# SenseLora_4G_LTE_CAT1_Gateway_V1_2.net
KiCad netlist of a schematic drawn in EAGLE
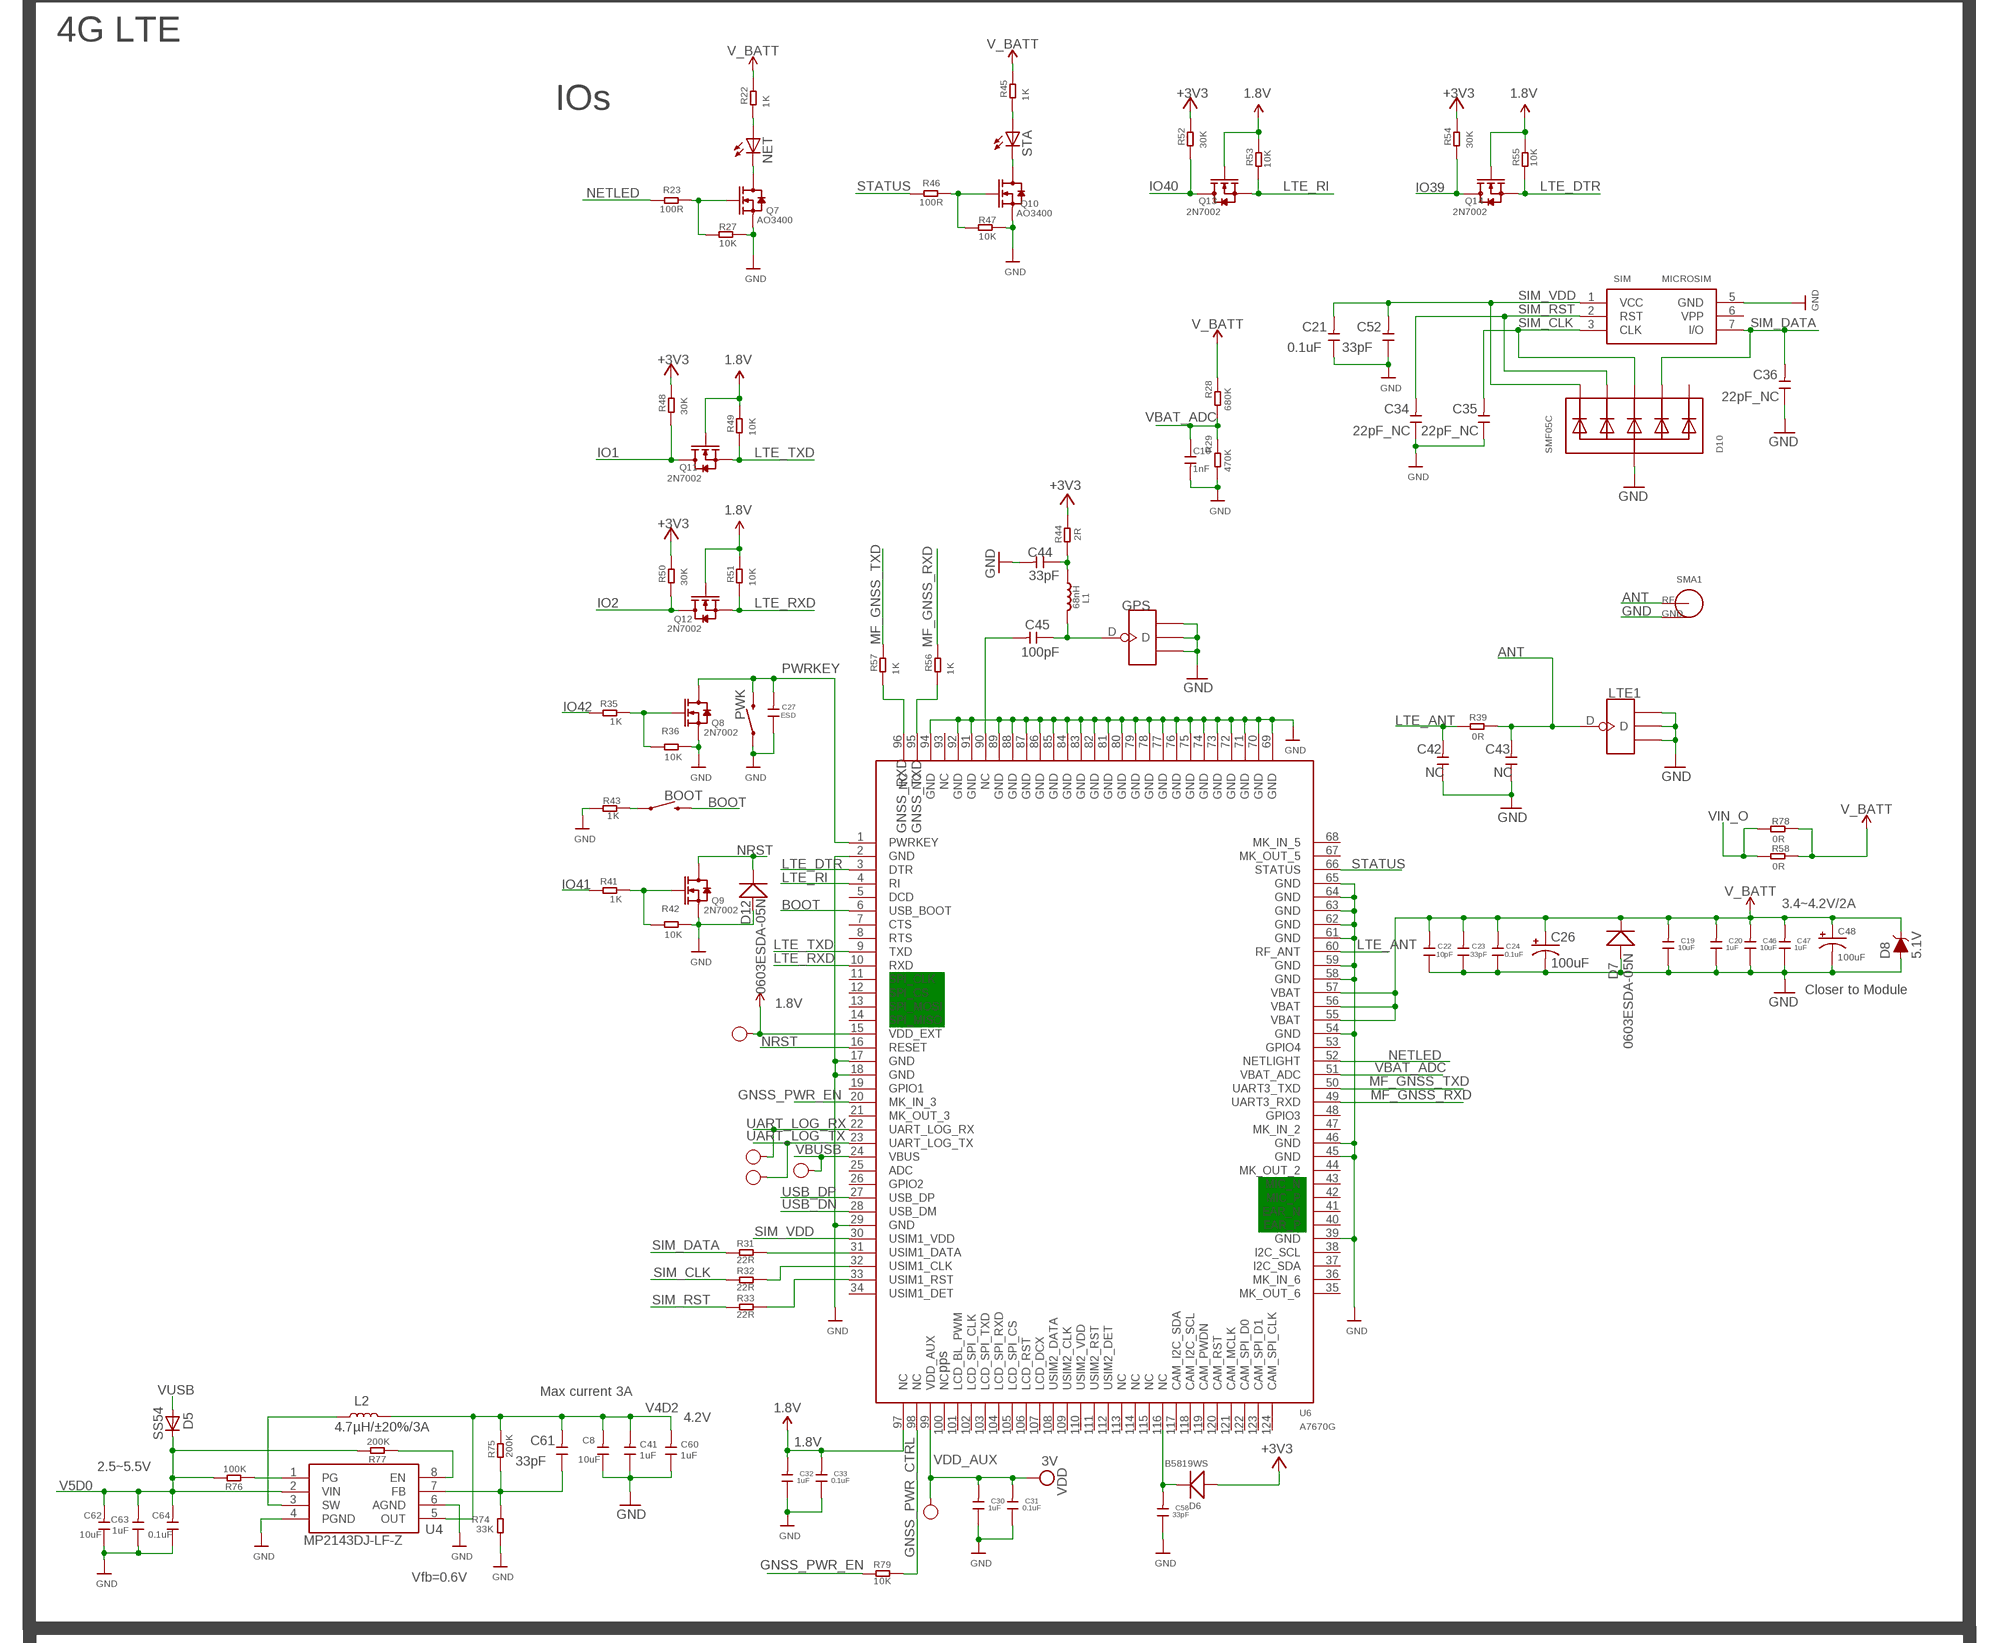
[diagram p0: schematic, sheet 1, part 1 of 2]
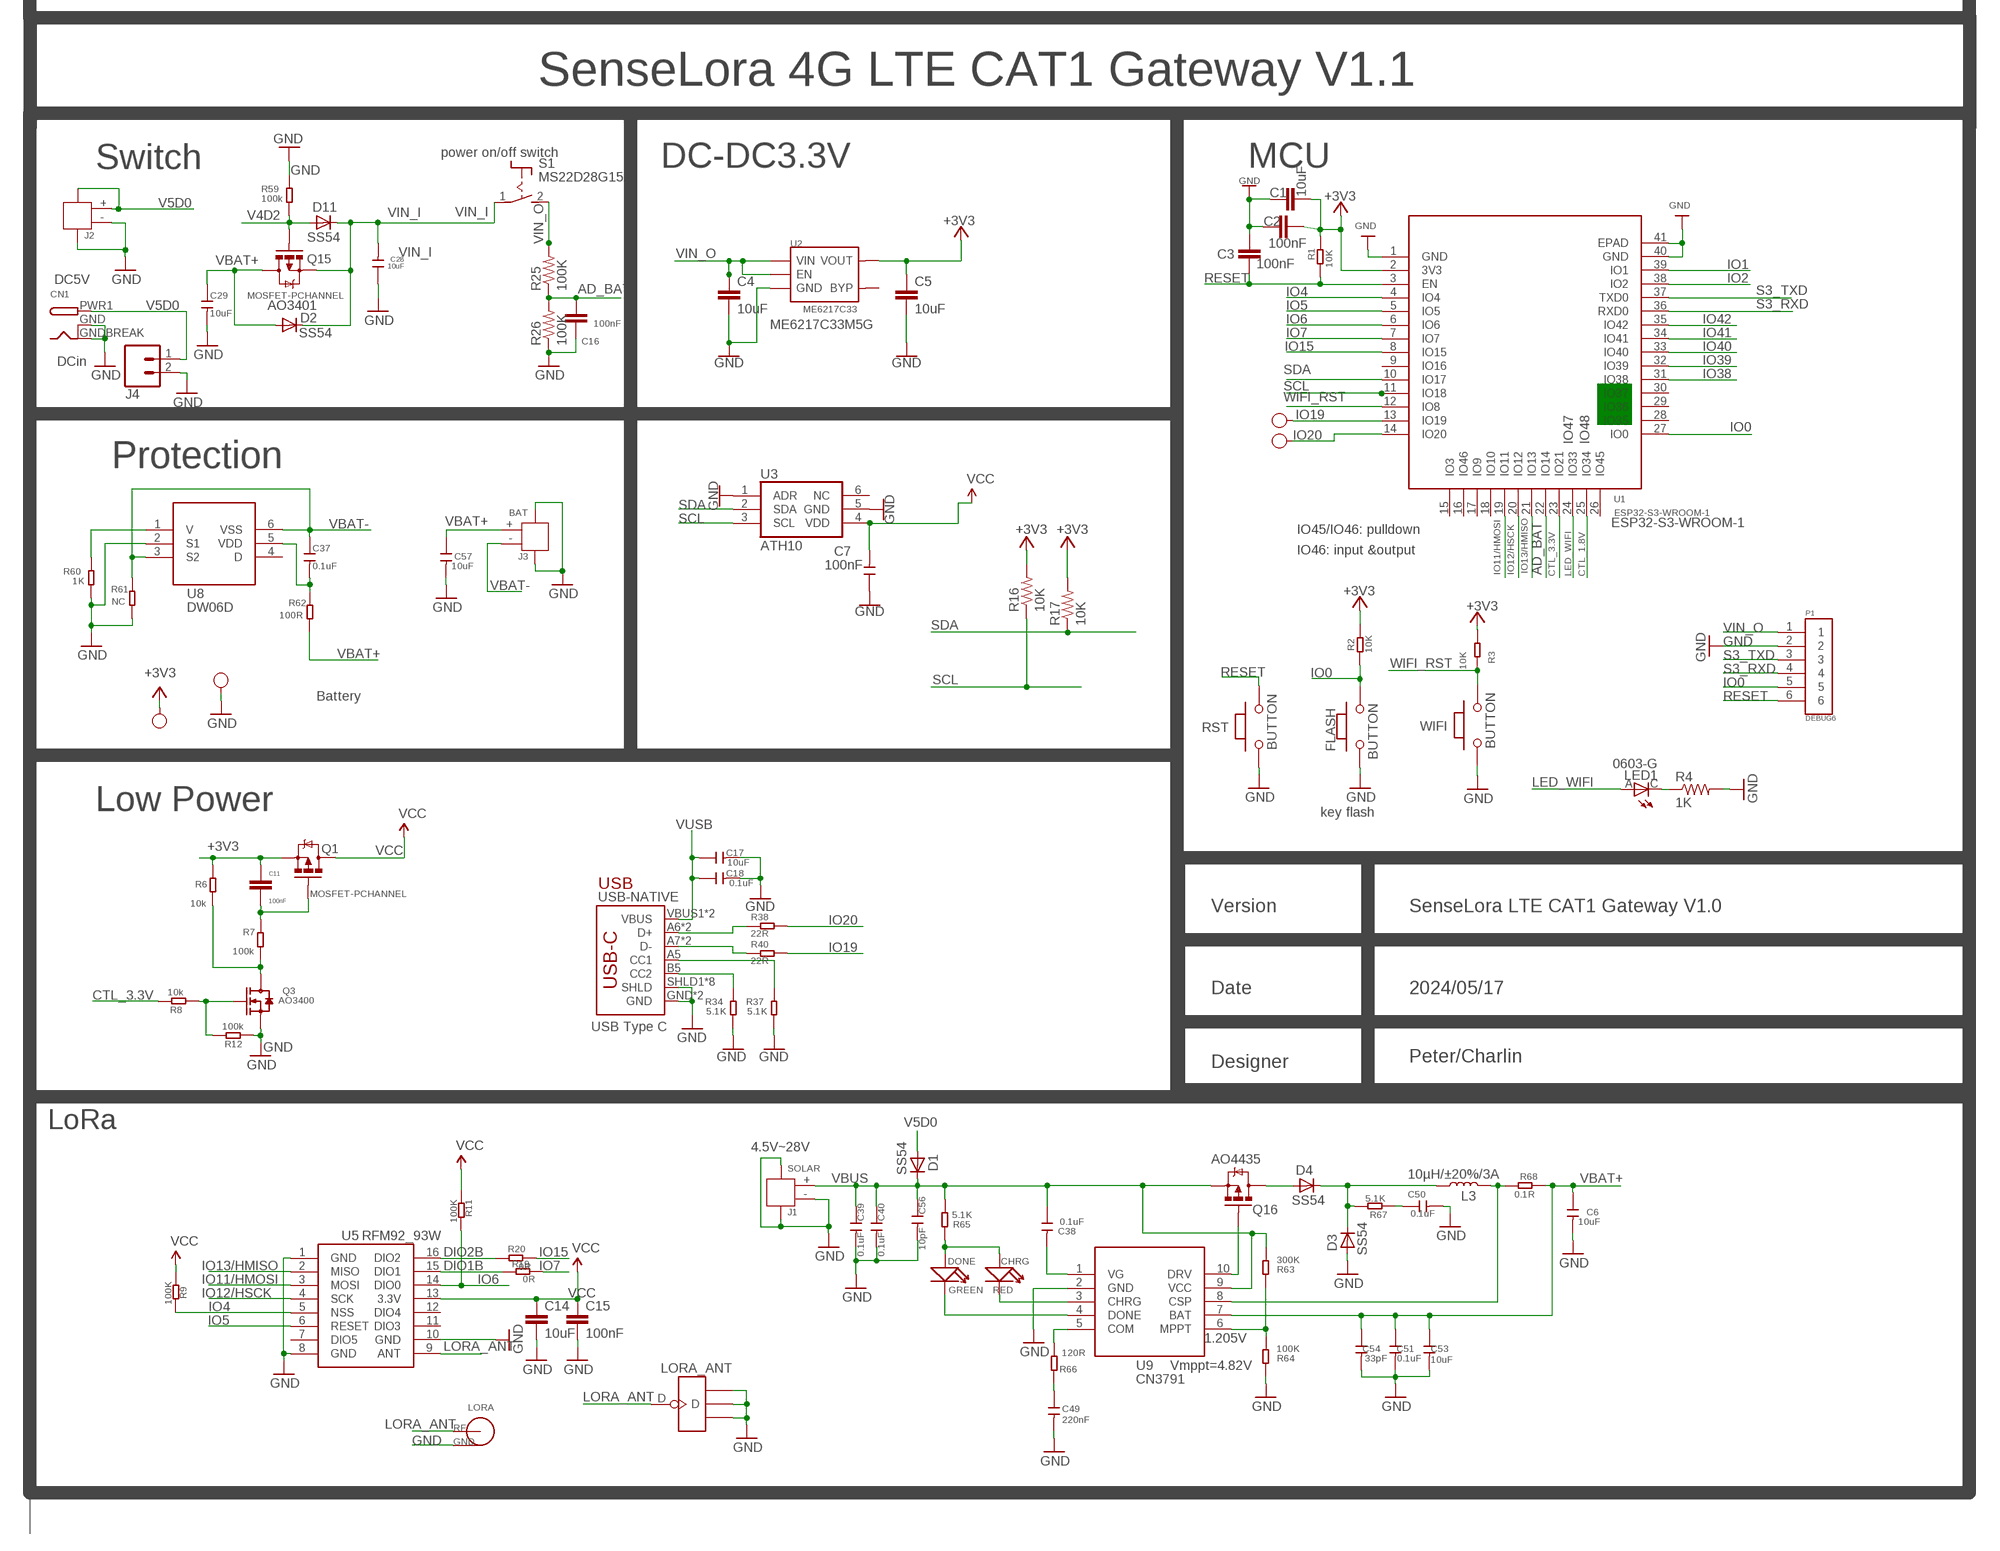
[diagram p1: schematic, sheet 1, part 2 of 2]

(export (version "E")
  (design (tool "Eeschema 10.0.6"))
  (components
    (comp (ref "1V8")
      (value "TEST-POINT'4545'")
      (footprint "eagle-import:TP-D45MIL")
      (fields (field (name "PARTNO") "DNP") (field (name "PARTNO_1") "DNP"))
      (libsource (lib "eagle-import") (part "TEST-POINT'4545'"))
    )
    (comp (ref "3V")
      (value "TEST-POINT'4545'")
      (footprint "eagle-import:TP-D45MIL")
      (fields (field (name "PARTNO") "DNP") (field (name "PARTNO_1") "DNP"))
      (libsource (lib "eagle-import") (part "TEST-POINT'4545'"))
    )
    (comp (ref "3V1")
      (value "TEST-POINT'4545'")
      (footprint "eagle-import:TP-D45MIL")
      (fields (field (name "PARTNO") "DNP") (field (name "PARTNO_1") "DNP"))
      (libsource (lib "eagle-import") (part "TEST-POINT'4545'"))
    )
    (comp (ref "3V2")
      (value "TEST-POINT'4545'")
      (footprint "eagle-import:TP-D45MIL")
      (fields (field (name "PARTNO") "DNP") (field (name "PARTNO_1") "DNP"))
      (libsource (lib "eagle-import") (part "TEST-POINT'4545'"))
    )
    (comp (ref "3V3")
      (value "TEST-POINT'4545'")
      (footprint "eagle-import:TP-D45MIL")
      (fields (field (name "PARTNO") "DNP") (field (name "PARTNO_1") "DNP"))
      (libsource (lib "eagle-import") (part "TEST-POINT'4545'"))
    )
    (comp (ref "BOOT")
      (value "MOMENTARY-SWITCH-SPST-SMD-6.0X3.5MM")
      (footprint "eagle-import:TACTILE_SWITCH_SMD_6.0X3.5MM")
      (fields (field (name "PROD_ID") "SWCH-00815") (field (name "SF_SKU") "COM-08229"))
      (libsource (lib "eagle-import") (part "MOMENTARY-SWITCH-SPST-SMD-6.0X3.5MM"))
    )
    (comp (ref "C1")
      (value "10uF")
      (footprint "eagle-import:C0603")
      (libsource (lib "eagle-import") (part "C0603"))
    )
    (comp (ref "C2")
      (value "100nF")
      (footprint "eagle-import:C0603")
      (libsource (lib "eagle-import") (part "C0603"))
    )
    (comp (ref "C3")
      (value "100nF")
      (footprint "eagle-import:C0603")
      (libsource (lib "eagle-import") (part "C0603"))
    )
    (comp (ref "C4")
      (value "10uF")
      (footprint "eagle-import:C0603")
      (libsource (lib "eagle-import") (part "C0603"))
    )
    (comp (ref "C5")
      (value "10uF")
      (footprint "eagle-import:C0603")
      (libsource (lib "eagle-import") (part "C0603"))
    )
    (comp (ref "C6")
      (value "10uF")
      (footprint "eagle-import:DISCRETE_C0603")
      (libsource (lib "eagle-import") (part "DISCRETE_C-0603"))
    )
    (comp (ref "C7")
      (value "100nF")
      (footprint "eagle-import:0603")
      (libsource (lib "eagle-import") (part "C-0603"))
    )
    (comp (ref "C8")
      (value "10uF")
      (footprint "eagle-import:0603")
      (libsource (lib "eagle-import") (part "C-0603"))
    )
    (comp (ref "C10")
      (value "1nF")
      (footprint "eagle-import:0603")
      (libsource (lib "eagle-import") (part "C-0603"))
    )
    (comp (ref "C11")
      (value "100nF")
      (footprint "eagle-import:C0603")
      (libsource (lib "eagle-import") (part "C0603"))
    )
    (comp (ref "C14")
      (value "10uF")
      (footprint "eagle-import:C0603")
      (libsource (lib "eagle-import") (part "C0603"))
    )
    (comp (ref "C15")
      (value "100nF")
      (footprint "eagle-import:C0603")
      (libsource (lib "eagle-import") (part "C0603"))
    )
    (comp (ref "C16")
      (value "100nF")
      (footprint "eagle-import:C0603")
      (libsource (lib "eagle-import") (part "C0603"))
    )
    (comp (ref "C17")
      (value "10uF")
      (footprint "eagle-import:0603")
      (libsource (lib "eagle-import") (part "C-0603"))
    )
    (comp (ref "C18")
      (value "0.1uF")
      (footprint "eagle-import:0603")
      (libsource (lib "eagle-import") (part "C-0603"))
    )
    (comp (ref "C19")
      (value "10uF")
      (footprint "eagle-import:0603")
      (libsource (lib "eagle-import") (part "C-0603"))
    )
    (comp (ref "C20")
      (value "1uF")
      (footprint "eagle-import:0603")
      (libsource (lib "eagle-import") (part "C-0603"))
    )
    (comp (ref "C21")
      (value "0.1uF")
      (footprint "eagle-import:0603")
      (libsource (lib "eagle-import") (part "C-0603"))
    )
    (comp (ref "C22")
      (value "10pF")
      (footprint "eagle-import:0603")
      (libsource (lib "eagle-import") (part "C-0603"))
    )
    (comp (ref "C23")
      (value "33pF")
      (footprint "eagle-import:0603")
      (libsource (lib "eagle-import") (part "C-0603"))
    )
    (comp (ref "C24")
      (value "0.1uF")
      (footprint "eagle-import:0603")
      (libsource (lib "eagle-import") (part "C-0603"))
    )
    (comp (ref "C26")
      (value "100uF")
      (footprint "eagle-import:EIA3528")
      (fields (field (name "PROD_ID") "CAP-10790"))
      (libsource (lib "eagle-import") (part "68UF-POLAR-EIA3528-10V-10%(TANT)"))
    )
    (comp (ref "C27")
      (value "ESD")
      (footprint "eagle-import:0603")
      (libsource (lib "eagle-import") (part "C-0603"))
    )
    (comp (ref "C28")
      (value "10uF")
      (footprint "eagle-import:0603")
      (libsource (lib "eagle-import") (part "C-0603"))
    )
    (comp (ref "C29")
      (value "10uF")
      (footprint "eagle-import:0603")
      (libsource (lib "eagle-import") (part "C-0603"))
    )
    (comp (ref "C30")
      (value "1uF")
      (footprint "eagle-import:0603")
      (libsource (lib "eagle-import") (part "C-0603"))
    )
    (comp (ref "C31")
      (value "0.1uF")
      (footprint "eagle-import:0603")
      (libsource (lib "eagle-import") (part "C-0603"))
    )
    (comp (ref "C32")
      (value "1uF")
      (footprint "eagle-import:0603")
      (libsource (lib "eagle-import") (part "C-0603"))
    )
    (comp (ref "C33")
      (value "0.1uF")
      (footprint "eagle-import:0603")
      (libsource (lib "eagle-import") (part "C-0603"))
    )
    (comp (ref "C34")
      (value "22pF_NC")
      (footprint "eagle-import:0603")
      (libsource (lib "eagle-import") (part "C-0603"))
    )
    (comp (ref "C35")
      (value "22pF_NC")
      (footprint "eagle-import:0603")
      (libsource (lib "eagle-import") (part "C-0603"))
    )
    (comp (ref "C36")
      (value "22pF_NC")
      (footprint "eagle-import:0603")
      (libsource (lib "eagle-import") (part "C-0603"))
    )
    (comp (ref "C37")
      (value "0.1uF")
      (footprint "eagle-import:0603")
      (libsource (lib "eagle-import") (part "C-0603"))
    )
    (comp (ref "C38")
      (value "0.1uF")
      (footprint "eagle-import:DISCRETE_C0603")
      (libsource (lib "eagle-import") (part "DISCRETE_C-0603"))
    )
    (comp (ref "C39")
      (value "0.1uF")
      (footprint "eagle-import:DISCRETE_C0603")
      (libsource (lib "eagle-import") (part "DISCRETE_C-0603"))
    )
    (comp (ref "C40")
      (value "0.1uF")
      (footprint "eagle-import:DISCRETE_C0603")
      (libsource (lib "eagle-import") (part "DISCRETE_C-0603"))
    )
    (comp (ref "C41")
      (value "1uF")
      (footprint "eagle-import:0603")
      (libsource (lib "eagle-import") (part "C-0603"))
    )
    (comp (ref "C42")
      (value "NC")
      (footprint "eagle-import:0603")
      (libsource (lib "eagle-import") (part "C-0603"))
    )
    (comp (ref "C43")
      (value "NC")
      (footprint "eagle-import:0603")
      (libsource (lib "eagle-import") (part "C-0603"))
    )
    (comp (ref "C44")
      (value "33pF")
      (footprint "eagle-import:0603")
      (libsource (lib "eagle-import") (part "C-0603"))
    )
    (comp (ref "C45")
      (value "100pF")
      (footprint "eagle-import:0603")
      (libsource (lib "eagle-import") (part "C-0603"))
    )
    (comp (ref "C46")
      (value "10uF")
      (footprint "eagle-import:0603")
      (libsource (lib "eagle-import") (part "C-0603"))
    )
    (comp (ref "C47")
      (value "1uF")
      (footprint "eagle-import:0603")
      (libsource (lib "eagle-import") (part "C-0603"))
    )
    (comp (ref "C48")
      (value "100uF")
      (footprint "eagle-import:EIA3528")
      (libsource (lib "eagle-import") (part "68UF-POLAR-EIA3528-10V-10%(TANT)"))
    )
    (comp (ref "C49")
      (value "220nF")
      (footprint "eagle-import:DISCRETE_C0603")
      (libsource (lib "eagle-import") (part "DISCRETE_C-0603"))
    )
    (comp (ref "C50")
      (value "0.1uF")
      (footprint "eagle-import:DISCRETE_C0603")
      (libsource (lib "eagle-import") (part "DISCRETE_C-0603"))
    )
    (comp (ref "C51")
      (value "0.1uF")
      (footprint "eagle-import:DISCRETE_C0603")
      (libsource (lib "eagle-import") (part "DISCRETE_C-0603"))
    )
    (comp (ref "C52")
      (value "33pF")
      (footprint "eagle-import:0603")
      (libsource (lib "eagle-import") (part "C-0603"))
    )
    (comp (ref "C53")
      (value "10uF")
      (footprint "eagle-import:DISCRETE_C0603")
      (libsource (lib "eagle-import") (part "DISCRETE_C-0603"))
    )
    (comp (ref "C54")
      (value "33pF")
      (footprint "eagle-import:DISCRETE_C0603")
      (libsource (lib "eagle-import") (part "DISCRETE_C-0603"))
    )
    (comp (ref "C56")
      (value "10pF")
      (footprint "eagle-import:DISCRETE_C0603")
      (libsource (lib "eagle-import") (part "DISCRETE_C-0603"))
    )
    (comp (ref "C57")
      (value "10uF")
      (footprint "eagle-import:DISCRETE_C0603")
      (libsource (lib "eagle-import") (part "DISCRETE_C-0603"))
    )
    (comp (ref "C58")
      (value "33pF")
      (footprint "eagle-import:0603")
      (libsource (lib "eagle-import") (part "C-0603"))
    )
    (comp (ref "C60")
      (value "1uF")
      (footprint "eagle-import:0603")
      (libsource (lib "eagle-import") (part "C-0603"))
    )
    (comp (ref "C61")
      (value "33pF")
      (footprint "eagle-import:0603")
      (libsource (lib "eagle-import") (part "C-0603"))
    )
    (comp (ref "C62")
      (value "10uF")
      (footprint "eagle-import:0603")
      (libsource (lib "eagle-import") (part "C-0603"))
    )
    (comp (ref "C63")
      (value "1uF")
      (footprint "eagle-import:0603")
      (libsource (lib "eagle-import") (part "C-0603"))
    )
    (comp (ref "C64")
      (value "0.1uF")
      (footprint "eagle-import:0603")
      (libsource (lib "eagle-import") (part "C-0603"))
    )
    (comp (ref "CHRG")
      (value "RED")
      (footprint "eagle-import:LED-0603")
      (libsource (lib "eagle-import") (part "LED'0603'"))
    )
    (comp (ref "CN1")
      (value "DCBARRELSMT")
      (footprint "eagle-import:DCJACK_2MM_SMT")
      (libsource (lib "eagle-import") (part "DCBARRELSMT"))
    )
    (comp (ref "D1")
      (value "SS54")
      (footprint "eagle-import:DO-214AC")
      (libsource (lib "eagle-import") (part "DIODE-DO-214AC"))
    )
    (comp (ref "D2")
      (value "SS54")
      (footprint "eagle-import:DO-214AC")
      (libsource (lib "eagle-import") (part "DIODE-DO-214AC"))
    )
    (comp (ref "D3")
      (value "SS54")
      (footprint "eagle-import:DO-214AC")
      (libsource (lib "eagle-import") (part "DIODE-DO-214AC"))
    )
    (comp (ref "D4")
      (value "SS54")
      (footprint "eagle-import:DO-214AC")
      (libsource (lib "eagle-import") (part "DIODE-DO-214AC"))
    )
    (comp (ref "D5")
      (value "SS54")
      (footprint "eagle-import:DO-214AC")
      (libsource (lib "eagle-import") (part "DIODE-DO-214AC"))
    )
    (comp (ref "D6")
      (value "B5819WS")
      (footprint "eagle-import:SOD323")
      (libsource (lib "eagle-import") (part "D'0805'"))
    )
    (comp (ref "D7")
      (value "0603ESDA-05N")
      (footprint "eagle-import:DISCRETE_SOD523")
      (libsource (lib "eagle-import") (part "DISCRETE_D0603"))
    )
    (comp (ref "D8")
      (value "5.1V")
      (footprint "eagle-import:SOD-323")
      (libsource (lib "eagle-import") (part "DIODE-ZENER-MMSZ5232BS"))
    )
    (comp (ref "D10")
      (value "SMF05C")
      (footprint "eagle-import:SOT363")
      (libsource (lib "eagle-import") (part "TVSARRAY_5LANE"))
    )
    (comp (ref "D11")
      (value "SS54")
      (footprint "eagle-import:DO-214AC")
      (libsource (lib "eagle-import") (part "DIODE-DO-214AC"))
    )
    (comp (ref "D12")
      (value "0603ESDA-05N")
      (footprint "eagle-import:DISCRETE_SOD523")
      (libsource (lib "eagle-import") (part "DISCRETE_D0603"))
    )
    (comp (ref "DONE")
      (value "GREEN")
      (footprint "eagle-import:LED-0603")
      (libsource (lib "eagle-import") (part "LED'0603'"))
    )
    (comp (ref "FLASH")
      (value "BUTTON")
      (footprint "eagle-import:157SW")
      (libsource (lib "eagle-import") (part "PB157"))
    )
    (comp (ref "GND")
      (value "TEST-POINT'4545'")
      (footprint "eagle-import:TP-D45MIL")
      (fields (field (name "PARTNO") "DNP") (field (name "PARTNO_1") "DNP"))
      (libsource (lib "eagle-import") (part "TEST-POINT'4545'"))
    )
    (comp (ref "GPS")
      (value "ANTENNA-U-FL")
      (footprint "eagle-import:4P-U-FL")
      (libsource (lib "eagle-import") (part "ANTENNA-U-FL"))
    )
    (comp (ref "J1")
      (value "SOLAR")
      (footprint "eagle-import:HW2-SMD-2.0-90D")
      (libsource (lib "eagle-import") (part "JST-2P-SMD'2.0'"))
    )
    (comp (ref "J2")
      (value "DC")
      (footprint "eagle-import:HW2-SMD-2.0-90D")
      (libsource (lib "eagle-import") (part "JST-2P-SMD'2.0'"))
    )
    (comp (ref "J3")
      (value "BAT")
      (footprint "eagle-import:HW2-SMD-2.0-90D")
      (libsource (lib "eagle-import") (part "JST-2P-SMD'2.0'"))
    )
    (comp (ref "J4")
      (value "CONN_02PTH4")
      (footprint "eagle-import:1X02_XTRA_BIG")
      (libsource (lib "eagle-import") (part "CONN_02PTH4"))
    )
    (comp (ref "L1")
      (value "68nH")
      (footprint "eagle-import:L0603")
      (libsource (lib "eagle-import") (part "L'0603'"))
    )
    (comp (ref "L2")
      (value "4.7µH/±20%/3A")
      (footprint "eagle-import:SRN6045")
      (libsource (lib "eagle-import") (part "INDUCTOR-SRN6045-33UH"))
    )
    (comp (ref "L3")
      (value "10µH/±20%/3A")
      (footprint "eagle-import:SRN6045")
      (libsource (lib "eagle-import") (part "INDUCTOR-SRN6045-33UH"))
    )
    (comp (ref "LED1")
      (value "0603-G")
      (footprint "eagle-import:LED0603")
      (libsource (lib "eagle-import") (part "LED0603"))
    )
    (comp (ref "LORA")
      (value "SMA-KWE")
      (footprint "eagle-import:SMA-KWE")
      (libsource (lib "eagle-import") (part "SMA-KWE"))
    )
    (comp (ref "LORA_ANT")
      (value "ANTENNA-U-FL")
      (footprint "eagle-import:4P-U-FL")
      (libsource (lib "eagle-import") (part "ANTENNA-U-FL"))
    )
    (comp (ref "LTE1")
      (value "ANTENNA-U-FL")
      (footprint "eagle-import:4P-U-FL")
      (libsource (lib "eagle-import") (part "ANTENNA-U-FL"))
    )
    (comp (ref "NET")
      (value "NET")
      (footprint "eagle-import:CHIP-LED0805")
      (libsource (lib "eagle-import") (part "LEDCHIP-LED0805"))
    )
    (comp (ref "P1")
      (value "DEBUG6")
      (footprint "eagle-import:DEBUG_6")
      (libsource (lib "eagle-import") (part "DEBUG6"))
    )
    (comp (ref "PWK")
      (value "MOMENTARY-SWITCH-SPST-SMD-6.0X3.5MM")
      (footprint "eagle-import:TACTILE_SWITCH_SMD_6.0X3.5MM")
      (libsource (lib "eagle-import") (part "MOMENTARY-SWITCH-SPST-SMD-6.0X3.5MM"))
    )
    (comp (ref "Q1")
      (value "MOSFET-PCHANNEL")
      (footprint "eagle-import:SOT23-3")
      (fields (field (name "PROD_ID") "TRANS-08285"))
      (libsource (lib "eagle-import") (part "MOSFET-PCHANNEL"))
    )
    (comp (ref "Q3")
      (value "AO3400")
      (footprint "eagle-import:SOT23")
      (libsource (lib "eagle-import") (part "MOSFET-N'SOT23'"))
    )
    (comp (ref "Q7")
      (value "AO3400")
      (footprint "eagle-import:SOT23")
      (libsource (lib "eagle-import") (part "MOSFET-N'SOT23'"))
    )
    (comp (ref "Q8")
      (value "2N7002")
      (footprint "eagle-import:SOT23")
      (libsource (lib "eagle-import") (part "MOSFET-N'SOT23'"))
    )
    (comp (ref "Q9")
      (value "2N7002")
      (footprint "eagle-import:SOT23")
      (libsource (lib "eagle-import") (part "MOSFET-N'SOT23'"))
    )
    (comp (ref "Q10")
      (value "AO3400")
      (footprint "eagle-import:SOT23")
      (libsource (lib "eagle-import") (part "MOSFET-N'SOT23'"))
    )
    (comp (ref "Q11")
      (value "2N7002")
      (footprint "eagle-import:SOT23")
      (libsource (lib "eagle-import") (part "MOSFET-N'SOT23'"))
    )
    (comp (ref "Q12")
      (value "2N7002")
      (footprint "eagle-import:SOT23")
      (libsource (lib "eagle-import") (part "MOSFET-N'SOT23'"))
    )
    (comp (ref "Q13")
      (value "2N7002")
      (footprint "eagle-import:SOT23")
      (libsource (lib "eagle-import") (part "MOSFET-N'SOT23'"))
    )
    (comp (ref "Q14")
      (value "2N7002")
      (footprint "eagle-import:SOT23")
      (libsource (lib "eagle-import") (part "MOSFET-N'SOT23'"))
    )
    (comp (ref "Q15")
      (value "MOSFET-PCHANNEL")
      (footprint "eagle-import:SOT23-3")
      (libsource (lib "eagle-import") (part "MOSFET-PCHANNEL"))
    )
    (comp (ref "Q16")
      (value "MOSFET-PCHANNELFDS6675")
      (footprint "eagle-import:SO08")
      (libsource (lib "eagle-import") (part "MOSFET-PCHANNELFDS6675"))
    )
    (comp (ref "R1")
      (value "10K")
      (footprint "eagle-import:R0603")
      (libsource (lib "eagle-import") (part "R-0603"))
    )
    (comp (ref "R2")
      (value "10K")
      (footprint "eagle-import:R0603")
      (libsource (lib "eagle-import") (part "R-0603"))
    )
    (comp (ref "R3")
      (value "10K")
      (footprint "eagle-import:R0603")
      (libsource (lib "eagle-import") (part "R-0603"))
    )
    (comp (ref "R4")
      (value "1K")
      (footprint "eagle-import:R0603")
      (libsource (lib "eagle-import") (part "R0603"))
    )
    (comp (ref "R6")
      (value "10k")
      (footprint "eagle-import:R0603")
      (libsource (lib "eagle-import") (part "R-0603"))
    )
    (comp (ref "R7")
      (value "100k")
      (footprint "eagle-import:R0603")
      (libsource (lib "eagle-import") (part "R-0603"))
    )
    (comp (ref "R8")
      (value "10k")
      (footprint "eagle-import:R0603")
      (libsource (lib "eagle-import") (part "R-0603"))
    )
    (comp (ref "R9")
      (value "100K")
      (footprint "eagle-import:R0603")
      (libsource (lib "eagle-import") (part "R-0603"))
    )
    (comp (ref "R11")
      (value "100K")
      (footprint "eagle-import:R0603")
      (libsource (lib "eagle-import") (part "R-0603"))
    )
    (comp (ref "R12")
      (value "100k")
      (footprint "eagle-import:R0603")
      (libsource (lib "eagle-import") (part "R-0603"))
    )
    (comp (ref "R16")
      (value "10K")
      (footprint "eagle-import:R0603")
      (libsource (lib "eagle-import") (part "R0603"))
    )
    (comp (ref "R17")
      (value "10K")
      (footprint "eagle-import:R0603")
      (libsource (lib "eagle-import") (part "R0603"))
    )
    (comp (ref "R19")
      (value "0R")
      (footprint "eagle-import:R0603")
      (libsource (lib "eagle-import") (part "R-0603"))
    )
    (comp (ref "R20")
      (value "0R")
      (footprint "eagle-import:R0603")
      (libsource (lib "eagle-import") (part "R-0603"))
    )
    (comp (ref "R22")
      (value "1K")
      (footprint "eagle-import:R0603")
      (libsource (lib "eagle-import") (part "R-0603"))
    )
    (comp (ref "R23")
      (value "100R")
      (footprint "eagle-import:R0603")
      (libsource (lib "eagle-import") (part "R-0603"))
    )
    (comp (ref "R25")
      (value "100K")
      (footprint "eagle-import:R0603")
      (libsource (lib "eagle-import") (part "R0603"))
    )
    (comp (ref "R26")
      (value "100K")
      (footprint "eagle-import:R0603")
      (libsource (lib "eagle-import") (part "R0603"))
    )
    (comp (ref "R27")
      (value "10K")
      (footprint "eagle-import:R0603")
      (libsource (lib "eagle-import") (part "R-0603"))
    )
    (comp (ref "R28")
      (value "680K")
      (footprint "eagle-import:R0603")
      (libsource (lib "eagle-import") (part "R-0603"))
    )
    (comp (ref "R29")
      (value "470K")
      (footprint "eagle-import:R0603")
      (libsource (lib "eagle-import") (part "R-0603"))
    )
    (comp (ref "R31")
      (value "22R")
      (footprint "eagle-import:R0603")
      (libsource (lib "eagle-import") (part "R-0603"))
    )
    (comp (ref "R32")
      (value "22R")
      (footprint "eagle-import:R0603")
      (libsource (lib "eagle-import") (part "R-0603"))
    )
    (comp (ref "R33")
      (value "22R")
      (footprint "eagle-import:R0603")
      (libsource (lib "eagle-import") (part "R-0603"))
    )
    (comp (ref "R34")
      (value "5.1K")
      (footprint "eagle-import:R0603")
      (libsource (lib "eagle-import") (part "R-0603"))
    )
    (comp (ref "R35")
      (value "1K")
      (footprint "eagle-import:R0603")
      (libsource (lib "eagle-import") (part "R-0603"))
    )
    (comp (ref "R36")
      (value "10K")
      (footprint "eagle-import:R0603")
      (libsource (lib "eagle-import") (part "R-0603"))
    )
    (comp (ref "R37")
      (value "5.1K")
      (footprint "eagle-import:R0603")
      (libsource (lib "eagle-import") (part "R-0603"))
    )
    (comp (ref "R38")
      (value "22R")
      (footprint "eagle-import:R0603")
      (libsource (lib "eagle-import") (part "R-0603"))
    )
    (comp (ref "R39")
      (value "0R")
      (footprint "eagle-import:R0603")
      (libsource (lib "eagle-import") (part "R-0603"))
    )
    (comp (ref "R40")
      (value "22R")
      (footprint "eagle-import:R0603")
      (libsource (lib "eagle-import") (part "R-0603"))
    )
    (comp (ref "R41")
      (value "1K")
      (footprint "eagle-import:R0603")
      (libsource (lib "eagle-import") (part "R-0603"))
    )
    (comp (ref "R42")
      (value "10K")
      (footprint "eagle-import:R0603")
      (libsource (lib "eagle-import") (part "R-0603"))
    )
    (comp (ref "R43")
      (value "1K")
      (footprint "eagle-import:R0603")
      (libsource (lib "eagle-import") (part "R-0603"))
    )
    (comp (ref "R44")
      (value "2R")
      (footprint "eagle-import:R0603")
      (libsource (lib "eagle-import") (part "R-0603"))
    )
    (comp (ref "R45")
      (value "1K")
      (footprint "eagle-import:R0603")
      (libsource (lib "eagle-import") (part "R-0603"))
    )
    (comp (ref "R46")
      (value "100R")
      (footprint "eagle-import:R0603")
      (libsource (lib "eagle-import") (part "R-0603"))
    )
    (comp (ref "R47")
      (value "10K")
      (footprint "eagle-import:R0603")
      (libsource (lib "eagle-import") (part "R-0603"))
    )
    (comp (ref "R48")
      (value "30K")
      (footprint "eagle-import:R0603")
      (libsource (lib "eagle-import") (part "R-0603"))
    )
    (comp (ref "R49")
      (value "10K")
      (footprint "eagle-import:R0603")
      (libsource (lib "eagle-import") (part "R-0603"))
    )
    (comp (ref "R50")
      (value "30K")
      (footprint "eagle-import:R0603")
      (libsource (lib "eagle-import") (part "R-0603"))
    )
    (comp (ref "R51")
      (value "10K")
      (footprint "eagle-import:R0603")
      (libsource (lib "eagle-import") (part "R-0603"))
    )
    (comp (ref "R52")
      (value "30K")
      (footprint "eagle-import:R0603")
      (libsource (lib "eagle-import") (part "R-0603"))
    )
    (comp (ref "R53")
      (value "10K")
      (footprint "eagle-import:R0603")
      (libsource (lib "eagle-import") (part "R-0603"))
    )
    (comp (ref "R54")
      (value "30K")
      (footprint "eagle-import:R0603")
      (libsource (lib "eagle-import") (part "R-0603"))
    )
    (comp (ref "R55")
      (value "10K")
      (footprint "eagle-import:R0603")
      (libsource (lib "eagle-import") (part "R-0603"))
    )
    (comp (ref "R56")
      (value "1K")
      (footprint "eagle-import:R0603")
      (libsource (lib "eagle-import") (part "R-0603"))
    )
    (comp (ref "R57")
      (value "1K")
      (footprint "eagle-import:R0603")
      (libsource (lib "eagle-import") (part "R-0603"))
    )
    (comp (ref "R58")
      (value "0R")
      (footprint "eagle-import:R0603")
      (libsource (lib "eagle-import") (part "R-0603"))
    )
    (comp (ref "R59")
      (value "100k")
      (footprint "eagle-import:R0603")
      (libsource (lib "eagle-import") (part "R-0603"))
    )
    (comp (ref "R60")
      (value "1K")
      (footprint "eagle-import:R0603")
      (libsource (lib "eagle-import") (part "R-0603"))
    )
    (comp (ref "R61")
      (value "NC")
      (footprint "eagle-import:R0603")
      (libsource (lib "eagle-import") (part "R-0603"))
    )
    (comp (ref "R62")
      (value "100R")
      (footprint "eagle-import:R0603")
      (libsource (lib "eagle-import") (part "R-0603"))
    )
    (comp (ref "R63")
      (value "300K")
      (footprint "eagle-import:DISCRETE_R0603")
      (libsource (lib "eagle-import") (part "DISCRETE_R-0603"))
    )
    (comp (ref "R64")
      (value "100K")
      (footprint "eagle-import:DISCRETE_R0603")
      (libsource (lib "eagle-import") (part "DISCRETE_R-0603"))
    )
    (comp (ref "R65")
      (value "5.1K")
      (footprint "eagle-import:DISCRETE_R0603")
      (libsource (lib "eagle-import") (part "DISCRETE_R-0603"))
    )
    (comp (ref "R66")
      (value "120R")
      (footprint "eagle-import:DISCRETE_R0603")
      (libsource (lib "eagle-import") (part "DISCRETE_R-0603"))
    )
    (comp (ref "R67")
      (value "5.1K")
      (footprint "eagle-import:DISCRETE_R0603")
      (libsource (lib "eagle-import") (part "DISCRETE_R-0603"))
    )
    (comp (ref "R68")
      (value "0.1R")
      (footprint "eagle-import:DISCRETE_R2512")
      (libsource (lib "eagle-import") (part "DISCRETE_R-2512"))
    )
    (comp (ref "R74")
      (value "33K")
      (footprint "eagle-import:R0603")
      (libsource (lib "eagle-import") (part "R-0603"))
    )
    (comp (ref "R75")
      (value "200K")
      (footprint "eagle-import:R0603")
      (libsource (lib "eagle-import") (part "R-0603"))
    )
    (comp (ref "R76")
      (value "100K")
      (footprint "eagle-import:R0603")
      (libsource (lib "eagle-import") (part "R-0603"))
    )
    (comp (ref "R77")
      (value "200K")
      (footprint "eagle-import:R0603")
      (libsource (lib "eagle-import") (part "R-0603"))
    )
    (comp (ref "R78")
      (value "0R")
      (footprint "eagle-import:R0603")
      (libsource (lib "eagle-import") (part "R-0603"))
    )
    (comp (ref "R79")
      (value "10K")
      (footprint "eagle-import:R0603")
      (libsource (lib "eagle-import") (part "R-0603"))
    )
    (comp (ref "RST")
      (value "BUTTON")
      (footprint "eagle-import:157SW")
      (libsource (lib "eagle-import") (part "PB157"))
    )
    (comp (ref "RX")
      (value "TEST-POINT'4545'")
      (footprint "eagle-import:TP-D45MIL")
      (fields (field (name "PARTNO") "DNP") (field (name "PARTNO_1") "DNP"))
      (libsource (lib "eagle-import") (part "TEST-POINT'4545'"))
    )
    (comp (ref "S1")
      (value "MS22D28G15")
      (footprint "eagle-import:S-MS22D28G15")
      (libsource (lib "eagle-import") (part "MS22D28G15"))
    )
    (comp (ref "SIM")
      (value "MICROSIM")
      (footprint "eagle-import:MICROSIM")
      (libsource (lib "eagle-import") (part "MICROSIM"))
    )
    (comp (ref "SMA1")
      (value "SMA-KWE")
      (footprint "eagle-import:SMA-KWE")
      (libsource (lib "eagle-import") (part "SMA-KWE"))
    )
    (comp (ref "STA")
      (value "NET")
      (footprint "eagle-import:CHIP-LED0805")
      (libsource (lib "eagle-import") (part "LEDCHIP-LED0805"))
    )
    (comp (ref "TX")
      (value "TEST-POINT'4545'")
      (footprint "eagle-import:TP-D45MIL")
      (fields (field (name "PARTNO") "DNP") (field (name "PARTNO_1") "DNP"))
      (libsource (lib "eagle-import") (part "TEST-POINT'4545'"))
    )
    (comp (ref "U1")
      (value "ESP32-S3-WROOM-1")
      (footprint "eagle-import:ESP32-­S2-­SOLO")
      (libsource (lib "eagle-import") (part "ESP32­S2­SOLO"))
    )
    (comp (ref "U2")
      (value "ME6217C33")
      (footprint "eagle-import:SOT23-5")
      (libsource (lib "eagle-import") (part "SPX3819"))
    )
    (comp (ref "U3")
      (value "ATH10")
      (footprint "eagle-import:AHT10")
      (libsource (lib "eagle-import") (part "ATH10"))
    )
    (comp (ref "U4")
      (value "MP2143DJ-LF-Z")
      (footprint "eagle-import:TSOT23-8")
      (libsource (lib "eagle-import") (part "MP2143DJ-LF-Z"))
    )
    (comp (ref "U5")
      (value "RFM92_93W")
      (footprint "eagle-import:RFM92_93W")
      (libsource (lib "eagle-import") (part "RFM92_93W"))
    )
    (comp (ref "U6")
      (value "A7670G")
      (footprint "eagle-import:A7670G")
      (libsource (lib "eagle-import") (part "A7670G"))
    )
    (comp (ref "U8")
      (value "DW06D")
      (footprint "eagle-import:SOT-23-6")
      (libsource (lib "eagle-import") (part "DW06D"))
    )
    (comp (ref "U9")
      (value "CN3791")
      (footprint "eagle-import:SSOP-10-150MIL")
      (libsource (lib "eagle-import") (part "CN3791"))
    )
    (comp (ref "USB-NATIVE")
      (value "USB_C5")
      (footprint "eagle-import:USB-C-16P-5")
      (libsource (lib "eagle-import") (part "USB_C5"))
    )
    (comp (ref "VU")
      (value "TEST-POINT'4545'")
      (footprint "eagle-import:TP-D45MIL")
      (fields (field (name "PARTNO") "DNP") (field (name "PARTNO_1") "DNP"))
      (libsource (lib "eagle-import") (part "TEST-POINT'4545'"))
    )
    (comp (ref "WIFI")
      (value "BUTTON")
      (footprint "eagle-import:157SW")
      (libsource (lib "eagle-import") (part "PB157"))
    )
  )
  (nets
    (net (code "1") (name "+3V3") (class "Default")
      (node (ref "3V3") (pin "T") (pinfunction "T_T") (pintype "bidirectional"))
      (node (ref "C1") (pin "2") (pinfunction "2_2") (pintype "passive"))
      (node (ref "C11") (pin "1") (pinfunction "1_1") (pintype "passive"))
      (node (ref "C2") (pin "2") (pinfunction "2_2") (pintype "passive"))
      (node (ref "C5") (pin "1") (pinfunction "1_1") (pintype "passive"))
      (node (ref "D6") (pin "+") (pinfunction "+_+") (pintype "passive"))
      (node (ref "Q1") (pin "2") (pinfunction "S_2") (pintype "passive"))
      (node (ref "R1") (pin "2") (pinfunction "2_2") (pintype "passive"))
      (node (ref "R16") (pin "2") (pinfunction "2_2") (pintype "passive"))
      (node (ref "R17") (pin "2") (pinfunction "2_2") (pintype "passive"))
      (node (ref "R2") (pin "2") (pinfunction "2_2") (pintype "passive"))
      (node (ref "R3") (pin "2") (pinfunction "2_2") (pintype "passive"))
      (node (ref "R44") (pin "2") (pinfunction "2_2") (pintype "passive"))
      (node (ref "R48") (pin "2") (pinfunction "2_2") (pintype "passive"))
      (node (ref "R50") (pin "2") (pinfunction "2_2") (pintype "passive"))
      (node (ref "R52") (pin "2") (pinfunction "2_2") (pintype "passive"))
      (node (ref "R54") (pin "2") (pinfunction "2_2") (pintype "passive"))
      (node (ref "R6") (pin "2") (pinfunction "2_2") (pintype "passive"))
      (node (ref "U1") (pin "2") (pinfunction "3V3_2") (pintype "bidirectional"))
      (node (ref "U2") (pin "5") (pinfunction "VOUT_5") (pintype "bidirectional"))
    )
    (net (code "2") (name "/AD_BAT") (class "Default")
      (node (ref "C16") (pin "2") (pinfunction "2_2") (pintype "passive"))
      (node (ref "R25") (pin "1") (pinfunction "1_1") (pintype "passive"))
      (node (ref "R26") (pin "2") (pinfunction "2_2") (pintype "passive"))
      (node (ref "U1") (pin "22") (pinfunction "IO14_22") (pintype "bidirectional"))
    )
    (net (code "3") (name "/ANT") (class "Default")
      (node (ref "C43") (pin "2") (pinfunction "2_2") (pintype "passive"))
      (node (ref "LTE1") (pin "D") (pinfunction "D_D") (pintype "bidirectional"))
      (node (ref "R39") (pin "2") (pinfunction "2_2") (pintype "passive"))
      (node (ref "SMA1") (pin "1") (pinfunction "SIG_1") (pintype "passive"))
    )
    (net (code "4") (name "/BOOT") (class "Default")
      (node (ref "BOOT") (pin "2") (pinfunction "2_2") (pintype "passive"))
      (node (ref "U6") (pin "6") (pinfunction "USB_BOOT_6") (pintype "bidirectional"))
    )
    (net (code "5") (name "/CTL_1.8V") (class "Default")
      (node (ref "U1") (pin "25") (pinfunction "IO34_25") (pintype "bidirectional"))
    )
    (net (code "6") (name "/CTL_3.3V") (class "Default")
      (node (ref "R8") (pin "2") (pinfunction "2_2") (pintype "passive"))
      (node (ref "U1") (pin "23") (pinfunction "IO21_23") (pintype "bidirectional"))
    )
    (net (code "7") (name "/DIO1B") (class "Default")
      (node (ref "R19") (pin "2") (pinfunction "2_2") (pintype "passive"))
      (node (ref "U5") (pin "15") (pinfunction "DIO1_15") (pintype "bidirectional"))
    )
    (net (code "8") (name "/DIO2B") (class "Default")
      (node (ref "R20") (pin "2") (pinfunction "2_2") (pintype "passive"))
      (node (ref "U5") (pin "16") (pinfunction "DIO2_16") (pintype "bidirectional"))
    )
    (net (code "9") (name "/GNSS_PWR_CTRL") (class "Default")
      (node (ref "R79") (pin "1") (pinfunction "1_1") (pintype "passive"))
      (node (ref "U6") (pin "98") (pinfunction "NC_98") (pintype "bidirectional"))
    )
    (net (code "10") (name "/GNSS_PWR_EN") (class "Default")
      (node (ref "R79") (pin "2") (pinfunction "2_2") (pintype "passive"))
      (node (ref "U6") (pin "20") (pinfunction "MK_IN_3_20") (pintype "bidirectional"))
    )
    (net (code "11") (name "/IO0") (class "Default")
      (node (ref "FLASH") (pin "2") (pinfunction "2_2") (pintype "passive"))
      (node (ref "P1") (pin "5") (pinfunction "5_5") (pintype "bidirectional"))
      (node (ref "R2") (pin "1") (pinfunction "1_1") (pintype "passive"))
      (node (ref "U1") (pin "27") (pinfunction "IO0_27") (pintype "bidirectional"))
    )
    (net (code "12") (name "/IO1") (class "Default")
      (node (ref "Q11") (pin "3") (pinfunction "D_3") (pintype "passive"))
      (node (ref "R48") (pin "1") (pinfunction "1_1") (pintype "passive"))
      (node (ref "U1") (pin "39") (pinfunction "IO1_39") (pintype "bidirectional"))
    )
    (net (code "13") (name "/IO2") (class "Default")
      (node (ref "Q12") (pin "3") (pinfunction "D_3") (pintype "passive"))
      (node (ref "R50") (pin "1") (pinfunction "1_1") (pintype "passive"))
      (node (ref "U1") (pin "38") (pinfunction "IO2_38") (pintype "bidirectional"))
    )
    (net (code "14") (name "/IO4") (class "Default")
      (node (ref "R9") (pin "1") (pinfunction "1_1") (pintype "passive"))
      (node (ref "U1") (pin "4") (pinfunction "IO4_4") (pintype "bidirectional"))
      (node (ref "U5") (pin "5") (pinfunction "NSS_5") (pintype "bidirectional"))
    )
    (net (code "15") (name "/IO5") (class "Default")
      (node (ref "U1") (pin "5") (pinfunction "IO5_5") (pintype "bidirectional"))
      (node (ref "U5") (pin "6") (pinfunction "RESET_6") (pintype "bidirectional"))
    )
    (net (code "16") (name "/IO6") (class "Default")
      (node (ref "R11") (pin "1") (pinfunction "1_1") (pintype "passive"))
      (node (ref "U1") (pin "6") (pinfunction "IO6_6") (pintype "bidirectional"))
      (node (ref "U5") (pin "14") (pinfunction "DIO0_14") (pintype "bidirectional"))
    )
    (net (code "17") (name "/IO7") (class "Default")
      (node (ref "R19") (pin "1") (pinfunction "1_1") (pintype "passive"))
      (node (ref "U1") (pin "7") (pinfunction "IO7_7") (pintype "bidirectional"))
    )
    (net (code "18") (name "/IO11{slash}HMOSI") (class "Default")
      (node (ref "U1") (pin "19") (pinfunction "IO11_19") (pintype "bidirectional"))
      (node (ref "U5") (pin "3") (pinfunction "MOSI_3") (pintype "bidirectional"))
    )
    (net (code "19") (name "/IO12{slash}HSCK") (class "Default")
      (node (ref "U1") (pin "20") (pinfunction "IO12_20") (pintype "bidirectional"))
      (node (ref "U5") (pin "4") (pinfunction "SCK_4") (pintype "bidirectional"))
    )
    (net (code "20") (name "/IO13{slash}HMISO") (class "Default")
      (node (ref "U1") (pin "21") (pinfunction "IO13_21") (pintype "bidirectional"))
      (node (ref "U5") (pin "2") (pinfunction "MISO_2") (pintype "bidirectional"))
    )
    (net (code "21") (name "/IO15") (class "Default")
      (node (ref "R20") (pin "1") (pinfunction "1_1") (pintype "passive"))
      (node (ref "U1") (pin "8") (pinfunction "IO15_8") (pintype "bidirectional"))
    )
    (net (code "22") (name "/IO19") (class "Default")
      (node (ref "3V1") (pin "T") (pinfunction "T_T") (pintype "bidirectional"))
      (node (ref "R40") (pin "1") (pinfunction "1_1") (pintype "passive"))
      (node (ref "U1") (pin "13") (pinfunction "IO19_13") (pintype "bidirectional"))
    )
    (net (code "23") (name "/IO20") (class "Default")
      (node (ref "3V2") (pin "T") (pinfunction "T_T") (pintype "bidirectional"))
      (node (ref "R38") (pin "1") (pinfunction "1_1") (pintype "passive"))
      (node (ref "U1") (pin "14") (pinfunction "IO20_14") (pintype "bidirectional"))
    )
    (net (code "24") (name "/IO38") (class "Default")
      (node (ref "U1") (pin "31") (pinfunction "IO38_31") (pintype "bidirectional"))
    )
    (net (code "25") (name "/IO39") (class "Default")
      (node (ref "Q14") (pin "3") (pinfunction "D_3") (pintype "passive"))
      (node (ref "R54") (pin "1") (pinfunction "1_1") (pintype "passive"))
      (node (ref "U1") (pin "32") (pinfunction "IO39_32") (pintype "bidirectional"))
    )
    (net (code "26") (name "/IO40") (class "Default")
      (node (ref "Q13") (pin "3") (pinfunction "D_3") (pintype "passive"))
      (node (ref "R52") (pin "1") (pinfunction "1_1") (pintype "passive"))
      (node (ref "U1") (pin "33") (pinfunction "IO40_33") (pintype "bidirectional"))
    )
    (net (code "27") (name "/IO41") (class "Default")
      (node (ref "R41") (pin "2") (pinfunction "2_2") (pintype "passive"))
      (node (ref "U1") (pin "34") (pinfunction "IO41_34") (pintype "bidirectional"))
    )
    (net (code "28") (name "/IO42") (class "Default")
      (node (ref "R35") (pin "2") (pinfunction "2_2") (pintype "passive"))
      (node (ref "U1") (pin "35") (pinfunction "IO42_35") (pintype "bidirectional"))
    )
    (net (code "29") (name "/LED_WIFI") (class "Default")
      (node (ref "LED1") (pin "A") (pinfunction "A_A") (pintype "passive"))
      (node (ref "U1") (pin "24") (pinfunction "IO33_24") (pintype "bidirectional"))
    )
    (net (code "30") (name "/LORA_ANT") (class "Default")
      (node (ref "LORA") (pin "1") (pinfunction "SIG_1") (pintype "passive"))
      (node (ref "LORA_ANT") (pin "D") (pinfunction "D_D") (pintype "bidirectional"))
      (node (ref "U5") (pin "9") (pinfunction "ANT_9") (pintype "bidirectional"))
    )
    (net (code "31") (name "/LTE_ANT") (class "Default")
      (node (ref "C42") (pin "2") (pinfunction "2_2") (pintype "passive"))
      (node (ref "R39") (pin "1") (pinfunction "1_1") (pintype "passive"))
      (node (ref "U6") (pin "60") (pinfunction "RF_ANT_60") (pintype "bidirectional"))
    )
    (net (code "32") (name "/LTE_DTR") (class "Default")
      (node (ref "Q14") (pin "2") (pinfunction "S_2") (pintype "passive"))
      (node (ref "R55") (pin "1") (pinfunction "1_1") (pintype "passive"))
      (node (ref "U6") (pin "3") (pinfunction "DTR_3") (pintype "bidirectional"))
    )
    (net (code "33") (name "/LTE_RI") (class "Default")
      (node (ref "Q13") (pin "2") (pinfunction "S_2") (pintype "passive"))
      (node (ref "R53") (pin "1") (pinfunction "1_1") (pintype "passive"))
      (node (ref "U6") (pin "4") (pinfunction "RI_4") (pintype "bidirectional"))
    )
    (net (code "34") (name "/LTE_RXD") (class "Default")
      (node (ref "Q12") (pin "2") (pinfunction "S_2") (pintype "passive"))
      (node (ref "R51") (pin "1") (pinfunction "1_1") (pintype "passive"))
      (node (ref "U6") (pin "10") (pinfunction "RXD_10") (pintype "bidirectional"))
    )
    (net (code "35") (name "/LTE_TXD") (class "Default")
      (node (ref "Q11") (pin "2") (pinfunction "S_2") (pintype "passive"))
      (node (ref "R49") (pin "1") (pinfunction "1_1") (pintype "passive"))
      (node (ref "U6") (pin "9") (pinfunction "TXD_9") (pintype "bidirectional"))
    )
    (net (code "36") (name "/MF_GNSS_RXD") (class "Default")
      (node (ref "R56") (pin "2") (pinfunction "2_2") (pintype "passive"))
      (node (ref "U6") (pin "49") (pinfunction "UART3_RXD_49") (pintype "bidirectional"))
    )
    (net (code "37") (name "/MF_GNSS_TXD") (class "Default")
      (node (ref "R57") (pin "2") (pinfunction "2_2") (pintype "passive"))
      (node (ref "U6") (pin "50") (pinfunction "UART3_TXD_50") (pintype "bidirectional"))
    )
    (net (code "38") (name "/NETLED") (class "Default")
      (node (ref "R23") (pin "2") (pinfunction "2_2") (pintype "passive"))
      (node (ref "U6") (pin "52") (pinfunction "NETLIGHT_52") (pintype "bidirectional"))
    )
    (net (code "39") (name "/NRST") (class "Default")
      (node (ref "D12") (pin "-") (pinfunction "-_-") (pintype "passive"))
      (node (ref "Q9") (pin "3") (pinfunction "D_3") (pintype "passive"))
      (node (ref "U6") (pin "16") (pinfunction "RESET_16") (pintype "bidirectional"))
    )
    (net (code "40") (name "/PWRKEY") (class "Default")
      (node (ref "C27") (pin "2") (pinfunction "2_2") (pintype "passive"))
      (node (ref "PWK") (pin "2") (pinfunction "2_2") (pintype "passive"))
      (node (ref "Q8") (pin "3") (pinfunction "D_3") (pintype "passive"))
      (node (ref "U6") (pin "1") (pinfunction "PWRKEY_1") (pintype "bidirectional"))
    )
    (net (code "41") (name "/RESET") (class "Default")
      (node (ref "C3") (pin "1") (pinfunction "1_1") (pintype "passive"))
      (node (ref "P1") (pin "6") (pinfunction "6_6") (pintype "bidirectional"))
      (node (ref "R1") (pin "1") (pinfunction "1_1") (pintype "passive"))
      (node (ref "RST") (pin "2") (pinfunction "2_2") (pintype "passive"))
      (node (ref "U1") (pin "3") (pinfunction "EN_3") (pintype "bidirectional"))
    )
    (net (code "42") (name "/S3_RXD") (class "Default")
      (node (ref "P1") (pin "4") (pinfunction "4_4") (pintype "bidirectional"))
      (node (ref "U1") (pin "36") (pinfunction "RXD0_36") (pintype "bidirectional"))
    )
    (net (code "43") (name "/S3_TXD") (class "Default")
      (node (ref "P1") (pin "3") (pinfunction "3_3") (pintype "bidirectional"))
      (node (ref "U1") (pin "37") (pinfunction "TXD0_37") (pintype "bidirectional"))
    )
    (net (code "44") (name "/SCL") (class "Default")
      (node (ref "R16") (pin "1") (pinfunction "1_1") (pintype "passive"))
      (node (ref "U1") (pin "11") (pinfunction "IO18_11") (pintype "bidirectional"))
      (node (ref "U3") (pin "3") (pinfunction "SCL_3") (pintype "bidirectional"))
    )
    (net (code "45") (name "/SDA") (class "Default")
      (node (ref "R17") (pin "1") (pinfunction "1_1") (pintype "passive"))
      (node (ref "U1") (pin "10") (pinfunction "IO17_10") (pintype "bidirectional"))
      (node (ref "U3") (pin "2") (pinfunction "SDA_2") (pintype "bidirectional"))
    )
    (net (code "46") (name "/SIM_CLK") (class "Default")
      (node (ref "C35") (pin "2") (pinfunction "2_2") (pintype "passive"))
      (node (ref "D10") (pin "4") (pinfunction "C3_4") (pintype "passive"))
      (node (ref "R32") (pin "2") (pinfunction "2_2") (pintype "passive"))
      (node (ref "SIM") (pin "3") (pinfunction "CLK_3") (pintype "bidirectional"))
    )
    (net (code "47") (name "/SIM_DATA") (class "Default")
      (node (ref "C36") (pin "2") (pinfunction "2_2") (pintype "passive"))
      (node (ref "D10") (pin "3") (pinfunction "C2_3") (pintype "passive"))
      (node (ref "R31") (pin "2") (pinfunction "2_2") (pintype "passive"))
      (node (ref "SIM") (pin "7") (pinfunction "I/O_7") (pintype "bidirectional"))
    )
    (net (code "48") (name "/SIM_RST") (class "Default")
      (node (ref "C34") (pin "2") (pinfunction "2_2") (pintype "passive"))
      (node (ref "D10") (pin "5") (pinfunction "C4_5") (pintype "passive"))
      (node (ref "R33") (pin "2") (pinfunction "2_2") (pintype "passive"))
      (node (ref "SIM") (pin "2") (pinfunction "RST_2") (pintype "bidirectional"))
    )
    (net (code "49") (name "/SIM_VDD") (class "Default")
      (node (ref "C21") (pin "2") (pinfunction "2_2") (pintype "passive"))
      (node (ref "C52") (pin "2") (pinfunction "2_2") (pintype "passive"))
      (node (ref "D10") (pin "6") (pinfunction "C5_6") (pintype "passive"))
      (node (ref "SIM") (pin "1") (pinfunction "VCC_1") (pintype "bidirectional"))
      (node (ref "U6") (pin "30") (pinfunction "USIM1_VDD_30") (pintype "bidirectional"))
    )
    (net (code "50") (name "/STATUS") (class "Default")
      (node (ref "R46") (pin "2") (pinfunction "2_2") (pintype "passive"))
      (node (ref "U6") (pin "66") (pinfunction "STATUS_66") (pintype "bidirectional"))
    )
    (net (code "51") (name "/UART_LOG_RX") (class "Default")
      (node (ref "RX") (pin "T") (pinfunction "T_T") (pintype "bidirectional"))
      (node (ref "U6") (pin "22") (pinfunction "UART_LOG_RX_22") (pintype "bidirectional"))
    )
    (net (code "52") (name "/UART_LOG_TX") (class "Default")
      (node (ref "TX") (pin "T") (pinfunction "T_T") (pintype "bidirectional"))
      (node (ref "U6") (pin "23") (pinfunction "UART_LOG_TX_23") (pintype "bidirectional"))
    )
    (net (code "53") (name "/USB_DN") (class "Default")
      (node (ref "U6") (pin "28") (pinfunction "USB_DM_28") (pintype "bidirectional"))
    )
    (net (code "54") (name "/USB_DP") (class "Default")
      (node (ref "U6") (pin "27") (pinfunction "USB_DP_27") (pintype "bidirectional"))
    )
    (net (code "55") (name "/V4D2") (class "Default")
      (node (ref "C41") (pin "2") (pinfunction "2_2") (pintype "passive"))
      (node (ref "C60") (pin "2") (pinfunction "2_2") (pintype "passive"))
      (node (ref "C61") (pin "2") (pinfunction "2_2") (pintype "passive"))
      (node (ref "C8") (pin "2") (pinfunction "2_2") (pintype "passive"))
      (node (ref "D11") (pin "A") (pinfunction "A_A") (pintype "passive"))
      (node (ref "L2") (pin "2") (pinfunction "2_2") (pintype "passive"))
      (node (ref "Q15") (pin "1") (pinfunction "G_1") (pintype "passive"))
      (node (ref "R59") (pin "1") (pinfunction "1_1") (pintype "passive"))
      (node (ref "R75") (pin "2") (pinfunction "2_2") (pintype "passive"))
      (node (ref "U4") (pin "5") (pinfunction "OUT_5") (pintype "bidirectional"))
    )
    (net (code "56") (name "/V5D0") (class "Default")
      (node (ref "C62") (pin "2") (pinfunction "2_2") (pintype "passive"))
      (node (ref "C63") (pin "2") (pinfunction "2_2") (pintype "passive"))
      (node (ref "C64") (pin "2") (pinfunction "2_2") (pintype "passive"))
      (node (ref "CN1") (pin "PWR1") (pinfunction "PWR_PWR1") (pintype "power_in"))
      (node (ref "D1") (pin "A") (pinfunction "A_A") (pintype "passive"))
      (node (ref "D5") (pin "C") (pinfunction "C_C") (pintype "passive"))
      (node (ref "J2") (pin "+") (pinfunction "1_+") (pintype "bidirectional"))
      (node (ref "J2") (pin "4") (pinfunction "4_4") (pintype "bidirectional"))
      (node (ref "J4") (pin "1") (pinfunction "1_1") (pintype "passive"))
      (node (ref "R76") (pin "2") (pinfunction "2_2") (pintype "passive"))
      (node (ref "R77") (pin "2") (pinfunction "2_2") (pintype "passive"))
      (node (ref "U4") (pin "2") (pinfunction "VIN_2") (pintype "bidirectional"))
    )
    (net (code "57") (name "/VBAT+") (class "Default")
      (node (ref "C29") (pin "1") (pinfunction "1_1") (pintype "passive"))
      (node (ref "C51") (pin "1") (pinfunction "1_1") (pintype "passive"))
      (node (ref "C53") (pin "1") (pinfunction "1_1") (pintype "passive"))
      (node (ref "C54") (pin "1") (pinfunction "1_1") (pintype "passive"))
      (node (ref "C57") (pin "1") (pinfunction "1_1") (pintype "passive"))
      (node (ref "C6") (pin "1") (pinfunction "1_1") (pintype "passive"))
      (node (ref "D2") (pin "A") (pinfunction "A_A") (pintype "passive"))
      (node (ref "J3") (pin "+") (pinfunction "1_+") (pintype "bidirectional"))
      (node (ref "Q15") (pin "3") (pinfunction "D_3") (pintype "passive"))
      (node (ref "R62") (pin "1") (pinfunction "1_1") (pintype "passive"))
      (node (ref "R68") (pin "2") (pinfunction "2_2") (pintype "passive"))
      (node (ref "U9") (pin "7") (pinfunction "BAT_7") (pintype "bidirectional"))
    )
    (net (code "58") (name "/VBAT-") (class "Default")
      (node (ref "C37") (pin "1") (pinfunction "1_1") (pintype "passive"))
      (node (ref "J3") (pin "-") (pinfunction "2_-") (pintype "bidirectional"))
      (node (ref "R61") (pin "2") (pinfunction "2_2") (pintype "passive"))
      (node (ref "U8") (pin "3") (pinfunction "S2_3") (pintype "bidirectional"))
      (node (ref "U8") (pin "6") (pinfunction "VSS_6") (pintype "bidirectional"))
    )
    (net (code "59") (name "/VBAT_ADC") (class "Default")
      (node (ref "C10") (pin "1") (pinfunction "1_1") (pintype "passive"))
      (node (ref "R28") (pin "1") (pinfunction "1_1") (pintype "passive"))
      (node (ref "R29") (pin "2") (pinfunction "2_2") (pintype "passive"))
      (node (ref "U6") (pin "51") (pinfunction "VBAT_ADC_51") (pintype "bidirectional"))
    )
    (net (code "60") (name "/VBUS") (class "Default")
      (node (ref "C38") (pin "1") (pinfunction "1_1") (pintype "passive"))
      (node (ref "C39") (pin "1") (pinfunction "1_1") (pintype "passive"))
      (node (ref "C40") (pin "1") (pinfunction "1_1") (pintype "passive"))
      (node (ref "C56") (pin "1") (pinfunction "1_1") (pintype "passive"))
      (node (ref "D1") (pin "C") (pinfunction "C_C") (pintype "passive"))
      (node (ref "J1") (pin "+") (pinfunction "1_+") (pintype "bidirectional"))
      (node (ref "Q16") (pin "1") (pinfunction "S_1") (pintype "passive"))
      (node (ref "Q16") (pin "2") (pinfunction "S_2") (pintype "passive"))
      (node (ref "Q16") (pin "3") (pinfunction "S_3") (pintype "passive"))
      (node (ref "R63") (pin "2") (pinfunction "2_2") (pintype "passive"))
      (node (ref "R65") (pin "2") (pinfunction "2_2") (pintype "passive"))
      (node (ref "U9") (pin "9") (pinfunction "VCC_9") (pintype "bidirectional"))
    )
    (net (code "61") (name "/VBUSB") (class "Default")
      (node (ref "U6") (pin "24") (pinfunction "VBUS_24") (pintype "bidirectional"))
      (node (ref "VU") (pin "T") (pinfunction "T_T") (pintype "bidirectional"))
    )
    (net (code "62") (name "/VIN_I") (class "Default")
      (node (ref "C28") (pin "2") (pinfunction "2_2") (pintype "passive"))
      (node (ref "D11") (pin "C") (pinfunction "C_C") (pintype "passive"))
      (node (ref "D2") (pin "C") (pinfunction "C_C") (pintype "passive"))
      (node (ref "Q15") (pin "2") (pinfunction "S_2") (pintype "passive"))
      (node (ref "S1") (pin "1") (pinfunction "P_1") (pintype "passive"))
    )
    (net (code "63") (name "/VIN_O") (class "Default")
      (node (ref "C4") (pin "1") (pinfunction "1_1") (pintype "passive"))
      (node (ref "P1") (pin "1") (pinfunction "1_1") (pintype "bidirectional"))
      (node (ref "R25") (pin "2") (pinfunction "2_2") (pintype "passive"))
      (node (ref "R58") (pin "2") (pinfunction "2_2") (pintype "passive"))
      (node (ref "R78") (pin "2") (pinfunction "2_2") (pintype "passive"))
      (node (ref "S1") (pin "2") (pinfunction "S_2") (pintype "passive"))
      (node (ref "U2") (pin "1") (pinfunction "VIN_1") (pintype "bidirectional"))
      (node (ref "U2") (pin "3") (pinfunction "EN_3") (pintype "bidirectional"))
    )
    (net (code "64") (name "/VUSB") (class "Default")
      (node (ref "C17") (pin "1") (pinfunction "1_1") (pintype "passive"))
      (node (ref "C18") (pin "1") (pinfunction "1_1") (pintype "passive"))
      (node (ref "D5") (pin "A") (pinfunction "A_A") (pintype "passive"))
      (node (ref "USB-NATIVE") (pin "VBUS1") (pinfunction "VBUS_VBUS1") (pintype "bidirectional"))
      (node (ref "USB-NATIVE") (pin "VBUS2") (pinfunction "VBUS_VBUS2") (pintype "bidirectional"))
    )
    (net (code "65") (name "/WIFI_RST") (class "Default")
      (node (ref "R3") (pin "1") (pinfunction "1_1") (pintype "passive"))
      (node (ref "U1") (pin "12") (pinfunction "IO8_12") (pintype "bidirectional"))
      (node (ref "WIFI") (pin "2") (pinfunction "2_2") (pintype "passive"))
    )
    (net (code "66") (name "1.8V") (class "Default")
      (node (ref "1V8") (pin "T") (pinfunction "T_T") (pintype "bidirectional"))
      (node (ref "C32") (pin "2") (pinfunction "2_2") (pintype "passive"))
      (node (ref "C33") (pin "2") (pinfunction "2_2") (pintype "passive"))
      (node (ref "Q11") (pin "1") (pinfunction "G_1") (pintype "passive"))
      (node (ref "Q12") (pin "1") (pinfunction "G_1") (pintype "passive"))
      (node (ref "Q13") (pin "1") (pinfunction "G_1") (pintype "passive"))
      (node (ref "Q14") (pin "1") (pinfunction "G_1") (pintype "passive"))
      (node (ref "R49") (pin "2") (pinfunction "2_2") (pintype "passive"))
      (node (ref "R51") (pin "2") (pinfunction "2_2") (pintype "passive"))
      (node (ref "R53") (pin "2") (pinfunction "2_2") (pintype "passive"))
      (node (ref "R55") (pin "2") (pinfunction "2_2") (pintype "passive"))
      (node (ref "U6") (pin "15") (pinfunction "VDD_EXT_15") (pintype "bidirectional"))
      (node (ref "U6") (pin "97") (pinfunction "NC_97") (pintype "bidirectional"))
    )
    (net (code "67") (name "GND") (class "Default")
      (node (ref "C1") (pin "1") (pinfunction "1_1") (pintype "passive"))
      (node (ref "C10") (pin "2") (pinfunction "2_2") (pintype "passive"))
      (node (ref "C14") (pin "2") (pinfunction "2_2") (pintype "passive"))
      (node (ref "C15") (pin "2") (pinfunction "2_2") (pintype "passive"))
      (node (ref "C16") (pin "1") (pinfunction "1_1") (pintype "passive"))
      (node (ref "C17") (pin "2") (pinfunction "2_2") (pintype "passive"))
      (node (ref "C18") (pin "2") (pinfunction "2_2") (pintype "passive"))
      (node (ref "C19") (pin "1") (pinfunction "1_1") (pintype "passive"))
      (node (ref "C2") (pin "1") (pinfunction "1_1") (pintype "passive"))
      (node (ref "C20") (pin "1") (pinfunction "1_1") (pintype "passive"))
      (node (ref "C21") (pin "1") (pinfunction "1_1") (pintype "passive"))
      (node (ref "C22") (pin "1") (pinfunction "1_1") (pintype "passive"))
      (node (ref "C23") (pin "1") (pinfunction "1_1") (pintype "passive"))
      (node (ref "C24") (pin "1") (pinfunction "1_1") (pintype "passive"))
      (node (ref "C26") (pin "C") (pinfunction "-_C") (pintype "passive"))
      (node (ref "C27") (pin "1") (pinfunction "1_1") (pintype "passive"))
      (node (ref "C28") (pin "1") (pinfunction "1_1") (pintype "passive"))
      (node (ref "C29") (pin "2") (pinfunction "2_2") (pintype "passive"))
      (node (ref "C3") (pin "2") (pinfunction "2_2") (pintype "passive"))
      (node (ref "C30") (pin "1") (pinfunction "1_1") (pintype "passive"))
      (node (ref "C31") (pin "1") (pinfunction "1_1") (pintype "passive"))
      (node (ref "C32") (pin "1") (pinfunction "1_1") (pintype "passive"))
      (node (ref "C33") (pin "1") (pinfunction "1_1") (pintype "passive"))
      (node (ref "C34") (pin "1") (pinfunction "1_1") (pintype "passive"))
      (node (ref "C35") (pin "1") (pinfunction "1_1") (pintype "passive"))
      (node (ref "C36") (pin "1") (pinfunction "1_1") (pintype "passive"))
      (node (ref "C39") (pin "2") (pinfunction "2_2") (pintype "passive"))
      (node (ref "C4") (pin "2") (pinfunction "2_2") (pintype "passive"))
      (node (ref "C40") (pin "2") (pinfunction "2_2") (pintype "passive"))
      (node (ref "C41") (pin "1") (pinfunction "1_1") (pintype "passive"))
      (node (ref "C42") (pin "1") (pinfunction "1_1") (pintype "passive"))
      (node (ref "C43") (pin "1") (pinfunction "1_1") (pintype "passive"))
      (node (ref "C44") (pin "2") (pinfunction "2_2") (pintype "passive"))
      (node (ref "C46") (pin "1") (pinfunction "1_1") (pintype "passive"))
      (node (ref "C47") (pin "1") (pinfunction "1_1") (pintype "passive"))
      (node (ref "C48") (pin "C") (pinfunction "-_C") (pintype "passive"))
      (node (ref "C49") (pin "2") (pinfunction "2_2") (pintype "passive"))
      (node (ref "C5") (pin "2") (pinfunction "2_2") (pintype "passive"))
      (node (ref "C50") (pin "2") (pinfunction "2_2") (pintype "passive"))
      (node (ref "C51") (pin "2") (pinfunction "2_2") (pintype "passive"))
      (node (ref "C52") (pin "1") (pinfunction "1_1") (pintype "passive"))
      (node (ref "C53") (pin "2") (pinfunction "2_2") (pintype "passive"))
      (node (ref "C54") (pin "2") (pinfunction "2_2") (pintype "passive"))
      (node (ref "C56") (pin "2") (pinfunction "2_2") (pintype "passive"))
      (node (ref "C57") (pin "2") (pinfunction "2_2") (pintype "passive"))
      (node (ref "C58") (pin "1") (pinfunction "1_1") (pintype "passive"))
      (node (ref "C6") (pin "2") (pinfunction "2_2") (pintype "passive"))
      (node (ref "C60") (pin "1") (pinfunction "1_1") (pintype "passive"))
      (node (ref "C62") (pin "1") (pinfunction "1_1") (pintype "passive"))
      (node (ref "C63") (pin "1") (pinfunction "1_1") (pintype "passive"))
      (node (ref "C64") (pin "1") (pinfunction "1_1") (pintype "passive"))
      (node (ref "C7") (pin "1") (pinfunction "1_1") (pintype "passive"))
      (node (ref "C8") (pin "1") (pinfunction "1_1") (pintype "passive"))
      (node (ref "CN1") (pin "GND") (pinfunction "GNDBREAK_GND") (pintype "power_in"))
      (node (ref "CN1") (pin "GNDBREAK") (pinfunction "GND_GNDBREAK") (pintype "power_in"))
      (node (ref "D10") (pin "2") (pinfunction "A_2") (pintype "passive"))
      (node (ref "D12") (pin "+") (pinfunction "+_+") (pintype "passive"))
      (node (ref "D3") (pin "A") (pinfunction "A_A") (pintype "passive"))
      (node (ref "D7") (pin "+") (pinfunction "+_+") (pintype "passive"))
      (node (ref "D8") (pin "A") (pinfunction "A_A") (pintype "passive"))
      (node (ref "FLASH") (pin "1") (pinfunction "1_1") (pintype "passive"))
      (node (ref "GND") (pin "T") (pinfunction "T_T") (pintype "bidirectional"))
      (node (ref "GPS") (pin "GND1") (pinfunction "GND1_GND1") (pintype "bidirectional"))
      (node (ref "GPS") (pin "GND2") (pinfunction "GND2_GND2") (pintype "bidirectional"))
      (node (ref "GPS") (pin "GND3") (pinfunction "GND3_GND3") (pintype "bidirectional"))
      (node (ref "J1") (pin "-") (pinfunction "2_-") (pintype "bidirectional"))
      (node (ref "J1") (pin "3") (pinfunction "3_3") (pintype "bidirectional"))
      (node (ref "J1") (pin "4") (pinfunction "4_4") (pintype "bidirectional"))
      (node (ref "J2") (pin "-") (pinfunction "2_-") (pintype "bidirectional"))
      (node (ref "J2") (pin "3") (pinfunction "3_3") (pintype "bidirectional"))
      (node (ref "J3") (pin "3") (pinfunction "3_3") (pintype "bidirectional"))
      (node (ref "J3") (pin "4") (pinfunction "4_4") (pintype "bidirectional"))
      (node (ref "J4") (pin "2") (pinfunction "2_2") (pintype "passive"))
      (node (ref "LORA") (pin "2") (pinfunction "GND_2") (pintype "passive"))
      (node (ref "LORA") (pin "3") (pinfunction "GND_3") (pintype "passive"))
      (node (ref "LORA") (pin "4") (pinfunction "GND_4") (pintype "passive"))
      (node (ref "LORA") (pin "5") (pinfunction "GND_5") (pintype "passive"))
      (node (ref "LORA_ANT") (pin "GND1") (pinfunction "GND1_GND1") (pintype "bidirectional"))
      (node (ref "LORA_ANT") (pin "GND2") (pinfunction "GND2_GND2") (pintype "bidirectional"))
      (node (ref "LORA_ANT") (pin "GND3") (pinfunction "GND3_GND3") (pintype "bidirectional"))
      (node (ref "LTE1") (pin "GND1") (pinfunction "GND1_GND1") (pintype "bidirectional"))
      (node (ref "LTE1") (pin "GND2") (pinfunction "GND2_GND2") (pintype "bidirectional"))
      (node (ref "LTE1") (pin "GND3") (pinfunction "GND3_GND3") (pintype "bidirectional"))
      (node (ref "P1") (pin "2") (pinfunction "2_2") (pintype "bidirectional"))
      (node (ref "PWK") (pin "1") (pinfunction "1_1") (pintype "passive"))
      (node (ref "Q10") (pin "2") (pinfunction "S_2") (pintype "passive"))
      (node (ref "Q3") (pin "2") (pinfunction "S_2") (pintype "passive"))
      (node (ref "Q7") (pin "2") (pinfunction "S_2") (pintype "passive"))
      (node (ref "Q8") (pin "2") (pinfunction "S_2") (pintype "passive"))
      (node (ref "Q9") (pin "2") (pinfunction "S_2") (pintype "passive"))
      (node (ref "R12") (pin "1") (pinfunction "1_1") (pintype "passive"))
      (node (ref "R26") (pin "1") (pinfunction "1_1") (pintype "passive"))
      (node (ref "R27") (pin "1") (pinfunction "1_1") (pintype "passive"))
      (node (ref "R29") (pin "1") (pinfunction "1_1") (pintype "passive"))
      (node (ref "R34") (pin "1") (pinfunction "1_1") (pintype "passive"))
      (node (ref "R36") (pin "1") (pinfunction "1_1") (pintype "passive"))
      (node (ref "R37") (pin "1") (pinfunction "1_1") (pintype "passive"))
      (node (ref "R4") (pin "2") (pinfunction "2_2") (pintype "passive"))
      (node (ref "R42") (pin "1") (pinfunction "1_1") (pintype "passive"))
      (node (ref "R43") (pin "2") (pinfunction "2_2") (pintype "passive"))
      (node (ref "R47") (pin "1") (pinfunction "1_1") (pintype "passive"))
      (node (ref "R59") (pin "2") (pinfunction "2_2") (pintype "passive"))
      (node (ref "R60") (pin "1") (pinfunction "1_1") (pintype "passive"))
      (node (ref "R61") (pin "1") (pinfunction "1_1") (pintype "passive"))
      (node (ref "R64") (pin "1") (pinfunction "1_1") (pintype "passive"))
      (node (ref "R74") (pin "1") (pinfunction "1_1") (pintype "passive"))
      (node (ref "RST") (pin "1") (pinfunction "1_1") (pintype "passive"))
      (node (ref "SIM") (pin "5") (pinfunction "GND_5") (pintype "bidirectional"))
      (node (ref "SMA1") (pin "2") (pinfunction "GND_2") (pintype "passive"))
      (node (ref "SMA1") (pin "3") (pinfunction "GND_3") (pintype "passive"))
      (node (ref "SMA1") (pin "4") (pinfunction "GND_4") (pintype "passive"))
      (node (ref "SMA1") (pin "5") (pinfunction "GND_5") (pintype "passive"))
      (node (ref "U1") (pin "1") (pinfunction "GND_1") (pintype "bidirectional"))
      (node (ref "U1") (pin "40") (pinfunction "GND_40") (pintype "bidirectional"))
      (node (ref "U1") (pin "41") (pinfunction "EPAD_41") (pintype "bidirectional"))
      (node (ref "U2") (pin "2") (pinfunction "GND_2") (pintype "bidirectional"))
      (node (ref "U3") (pin "1") (pinfunction "ADR_1") (pintype "bidirectional"))
      (node (ref "U3") (pin "5") (pinfunction "GND_5") (pintype "bidirectional"))
      (node (ref "U4") (pin "4") (pinfunction "PGND_4") (pintype "bidirectional"))
      (node (ref "U4") (pin "6") (pinfunction "AGND_6") (pintype "bidirectional"))
      (node (ref "U5") (pin "1") (pinfunction "GND_1") (pintype "power_in"))
      (node (ref "U5") (pin "10") (pinfunction "GND_10") (pintype "power_in"))
      (node (ref "U5") (pin "8") (pinfunction "GND_8") (pintype "power_in"))
      (node (ref "U6") (pin "17") (pinfunction "GND_17") (pintype "bidirectional"))
      (node (ref "U6") (pin "18") (pinfunction "GND_18") (pintype "bidirectional"))
      (node (ref "U6") (pin "2") (pinfunction "GND_2") (pintype "bidirectional"))
      (node (ref "U6") (pin "29") (pinfunction "GND_29") (pintype "bidirectional"))
      (node (ref "U6") (pin "39") (pinfunction "GND_39") (pintype "bidirectional"))
      (node (ref "U6") (pin "45") (pinfunction "GND_45") (pintype "bidirectional"))
      (node (ref "U6") (pin "46") (pinfunction "GND_46") (pintype "bidirectional"))
      (node (ref "U6") (pin "54") (pinfunction "GND_54") (pintype "bidirectional"))
      (node (ref "U6") (pin "58") (pinfunction "GND_58") (pintype "bidirectional"))
      (node (ref "U6") (pin "59") (pinfunction "GND_59") (pintype "bidirectional"))
      (node (ref "U6") (pin "61") (pinfunction "GND_61") (pintype "bidirectional"))
      (node (ref "U6") (pin "62") (pinfunction "GND_62") (pintype "bidirectional"))
      (node (ref "U6") (pin "63") (pinfunction "GND_63") (pintype "bidirectional"))
      (node (ref "U6") (pin "64") (pinfunction "GND_64") (pintype "bidirectional"))
      (node (ref "U6") (pin "65") (pinfunction "GND_65") (pintype "bidirectional"))
      (node (ref "U6") (pin "69") (pinfunction "GND_69") (pintype "bidirectional"))
      (node (ref "U6") (pin "70") (pinfunction "GND_70") (pintype "bidirectional"))
      (node (ref "U6") (pin "71") (pinfunction "GND_71") (pintype "bidirectional"))
      (node (ref "U6") (pin "72") (pinfunction "GND_72") (pintype "bidirectional"))
      (node (ref "U6") (pin "73") (pinfunction "GND_73") (pintype "bidirectional"))
      (node (ref "U6") (pin "74") (pinfunction "GND_74") (pintype "bidirectional"))
      (node (ref "U6") (pin "75") (pinfunction "GND_75") (pintype "bidirectional"))
      (node (ref "U6") (pin "76") (pinfunction "GND_76") (pintype "bidirectional"))
      (node (ref "U6") (pin "77") (pinfunction "GND_77") (pintype "bidirectional"))
      (node (ref "U6") (pin "78") (pinfunction "GND_78") (pintype "bidirectional"))
      (node (ref "U6") (pin "79") (pinfunction "GND_79") (pintype "bidirectional"))
      (node (ref "U6") (pin "80") (pinfunction "GND_80") (pintype "bidirectional"))
      (node (ref "U6") (pin "81") (pinfunction "GND_81") (pintype "bidirectional"))
      (node (ref "U6") (pin "82") (pinfunction "GND_82") (pintype "bidirectional"))
      (node (ref "U6") (pin "83") (pinfunction "GND_83") (pintype "bidirectional"))
      (node (ref "U6") (pin "84") (pinfunction "GND_84") (pintype "bidirectional"))
      (node (ref "U6") (pin "85") (pinfunction "GND_85") (pintype "bidirectional"))
      (node (ref "U6") (pin "86") (pinfunction "GND_86") (pintype "bidirectional"))
      (node (ref "U6") (pin "87") (pinfunction "GND_87") (pintype "bidirectional"))
      (node (ref "U6") (pin "88") (pinfunction "GND_88") (pintype "bidirectional"))
      (node (ref "U6") (pin "89") (pinfunction "GND_89") (pintype "bidirectional"))
      (node (ref "U6") (pin "91") (pinfunction "GND_91") (pintype "bidirectional"))
      (node (ref "U6") (pin "92") (pinfunction "GND_92") (pintype "bidirectional"))
      (node (ref "U6") (pin "94") (pinfunction "GND_94") (pintype "bidirectional"))
      (node (ref "U8") (pin "2") (pinfunction "S1_2") (pintype "bidirectional"))
      (node (ref "U9") (pin "2") (pinfunction "GND_2") (pintype "bidirectional"))
      (node (ref "USB-NATIVE") (pin "GND") (pinfunction "GND_GND") (pintype "bidirectional"))
      (node (ref "USB-NATIVE") (pin "GND2") (pinfunction "GND_GND2") (pintype "bidirectional"))
      (node (ref "USB-NATIVE") (pin "SHLD1") (pinfunction "SHLD_SHLD1") (pintype "bidirectional"))
      (node (ref "USB-NATIVE") (pin "SHLD2") (pinfunction "SHLD_SHLD2") (pintype "bidirectional"))
      (node (ref "USB-NATIVE") (pin "SHLD3") (pinfunction "SHLD_SHLD3") (pintype "bidirectional"))
      (node (ref "USB-NATIVE") (pin "SHLD4") (pinfunction "SHLD_SHLD4") (pintype "bidirectional"))
      (node (ref "USB-NATIVE") (pin "SHLD5") (pinfunction "SHLD_SHLD5") (pintype "bidirectional"))
      (node (ref "USB-NATIVE") (pin "SHLD6") (pinfunction "SHLD_SHLD6") (pintype "bidirectional"))
      (node (ref "USB-NATIVE") (pin "SHLD7") (pinfunction "SHLD_SHLD7") (pintype "bidirectional"))
      (node (ref "USB-NATIVE") (pin "SHLD8") (pinfunction "SHLD_SHLD8") (pintype "bidirectional"))
      (node (ref "WIFI") (pin "1") (pinfunction "1_1") (pintype "passive"))
    )
    (net (code "68") (name "Net-(BOOT-Pad1)") (class "Default")
      (node (ref "BOOT") (pin "1") (pinfunction "1_1") (pintype "passive"))
      (node (ref "R43") (pin "1") (pinfunction "1_1") (pintype "passive"))
    )
    (net (code "69") (name "Net-(C44-Pad1)") (class "Default")
      (node (ref "C44") (pin "1") (pinfunction "1_1") (pintype "passive"))
      (node (ref "L1") (pin "1") (pinfunction "1_1") (pintype "passive"))
      (node (ref "R44") (pin "1") (pinfunction "1_1") (pintype "passive"))
    )
    (net (code "70") (name "Net-(C45-Pad1)") (class "Default")
      (node (ref "C45") (pin "1") (pinfunction "1_1") (pintype "passive"))
      (node (ref "GPS") (pin "D") (pinfunction "D_D") (pintype "bidirectional"))
      (node (ref "L1") (pin "2") (pinfunction "2_2") (pintype "passive"))
    )
    (net (code "71") (name "Net-(C45-Pad2)") (class "Default")
      (node (ref "C45") (pin "2") (pinfunction "2_2") (pintype "passive"))
      (node (ref "U6") (pin "90") (pinfunction "NC_90") (pintype "bidirectional"))
    )
    (net (code "72") (name "Net-(C49-Pad1)") (class "Default")
      (node (ref "C49") (pin "1") (pinfunction "1_1") (pintype "passive"))
      (node (ref "R66") (pin "1") (pinfunction "1_1") (pintype "passive"))
    )
    (net (code "73") (name "Net-(C50-Pad1)") (class "Default")
      (node (ref "C50") (pin "1") (pinfunction "1_1") (pintype "passive"))
      (node (ref "R67") (pin "1") (pinfunction "1_1") (pintype "passive"))
    )
    (net (code "74") (name "Net-(C58-Pad2)") (class "Default")
      (node (ref "C58") (pin "2") (pinfunction "2_2") (pintype "passive"))
      (node (ref "D6") (pin "-") (pinfunction "-_-") (pintype "passive"))
      (node (ref "U6") (pin "116") (pinfunction "NC_116") (pintype "bidirectional"))
    )
    (net (code "75") (name "Net-(CHRG-Pad+)") (class "Default")
      (node (ref "CHRG") (pin "+") (pinfunction "+_+") (pintype "passive"))
      (node (ref "DONE") (pin "+") (pinfunction "+_+") (pintype "passive"))
      (node (ref "R65") (pin "1") (pinfunction "1_1") (pintype "passive"))
    )
    (net (code "76") (name "Net-(D3-PadC)") (class "Default")
      (node (ref "D3") (pin "C") (pinfunction "C_C") (pintype "passive"))
      (node (ref "D4") (pin "C") (pinfunction "C_C") (pintype "passive"))
      (node (ref "L3") (pin "1") (pinfunction "1_1") (pintype "passive"))
      (node (ref "R67") (pin "2") (pinfunction "2_2") (pintype "passive"))
    )
    (net (code "77") (name "Net-(D4-PadA)") (class "Default")
      (node (ref "D4") (pin "A") (pinfunction "A_A") (pintype "passive"))
      (node (ref "Q16") (pin "5") (pinfunction "D_5") (pintype "passive"))
      (node (ref "Q16") (pin "6") (pinfunction "D_6") (pintype "passive"))
      (node (ref "Q16") (pin "7") (pinfunction "D_7") (pintype "passive"))
      (node (ref "Q16") (pin "8") (pinfunction "D_8") (pintype "passive"))
    )
    (net (code "78") (name "Net-(LED1-PadC)") (class "Default")
      (node (ref "LED1") (pin "C") (pinfunction "C_C") (pintype "passive"))
      (node (ref "R4") (pin "1") (pinfunction "1_1") (pintype "passive"))
    )
    (net (code "79") (name "Net-(NET-PadA)") (class "Default")
      (node (ref "NET") (pin "A") (pinfunction "A_A") (pintype "passive"))
      (node (ref "R22") (pin "1") (pinfunction "1_1") (pintype "passive"))
    )
    (net (code "80") (name "Net-(Q1-G)") (class "Default")
      (node (ref "C11") (pin "2") (pinfunction "2_2") (pintype "passive"))
      (node (ref "Q1") (pin "1") (pinfunction "G_1") (pintype "passive"))
      (node (ref "R7") (pin "2") (pinfunction "2_2") (pintype "passive"))
    )
    (net (code "81") (name "Net-(Q3-D)") (class "Default")
      (node (ref "Q3") (pin "3") (pinfunction "D_3") (pintype "passive"))
      (node (ref "R6") (pin "1") (pinfunction "1_1") (pintype "passive"))
      (node (ref "R7") (pin "1") (pinfunction "1_1") (pintype "passive"))
    )
    (net (code "82") (name "Net-(Q3-G)") (class "Default")
      (node (ref "Q3") (pin "1") (pinfunction "G_1") (pintype "passive"))
      (node (ref "R12") (pin "2") (pinfunction "2_2") (pintype "passive"))
      (node (ref "R8") (pin "1") (pinfunction "1_1") (pintype "passive"))
    )
    (net (code "83") (name "Net-(Q7-D)") (class "Default")
      (node (ref "NET") (pin "C") (pinfunction "C_C") (pintype "passive"))
      (node (ref "Q7") (pin "3") (pinfunction "D_3") (pintype "passive"))
    )
    (net (code "84") (name "Net-(Q7-G)") (class "Default")
      (node (ref "Q7") (pin "1") (pinfunction "G_1") (pintype "passive"))
      (node (ref "R23") (pin "1") (pinfunction "1_1") (pintype "passive"))
      (node (ref "R27") (pin "2") (pinfunction "2_2") (pintype "passive"))
    )
    (net (code "85") (name "Net-(Q8-G)") (class "Default")
      (node (ref "Q8") (pin "1") (pinfunction "G_1") (pintype "passive"))
      (node (ref "R35") (pin "1") (pinfunction "1_1") (pintype "passive"))
      (node (ref "R36") (pin "2") (pinfunction "2_2") (pintype "passive"))
    )
    (net (code "86") (name "Net-(Q9-G)") (class "Default")
      (node (ref "Q9") (pin "1") (pinfunction "G_1") (pintype "passive"))
      (node (ref "R41") (pin "1") (pinfunction "1_1") (pintype "passive"))
      (node (ref "R42") (pin "2") (pinfunction "2_2") (pintype "passive"))
    )
    (net (code "87") (name "Net-(Q10-D)") (class "Default")
      (node (ref "Q10") (pin "3") (pinfunction "D_3") (pintype "passive"))
      (node (ref "STA") (pin "C") (pinfunction "C_C") (pintype "passive"))
    )
    (net (code "88") (name "Net-(Q10-G)") (class "Default")
      (node (ref "Q10") (pin "1") (pinfunction "G_1") (pintype "passive"))
      (node (ref "R46") (pin "1") (pinfunction "1_1") (pintype "passive"))
      (node (ref "R47") (pin "2") (pinfunction "2_2") (pintype "passive"))
    )
    (net (code "89") (name "Net-(Q16-G)") (class "Default")
      (node (ref "Q16") (pin "4") (pinfunction "G_4") (pintype "passive"))
      (node (ref "U9") (pin "10") (pinfunction "DRV_10") (pintype "bidirectional"))
    )
    (net (code "90") (name "Net-(R38-Pad2)") (class "Default")
      (node (ref "R38") (pin "2") (pinfunction "2_2") (pintype "passive"))
      (node (ref "USB-NATIVE") (pin "A6") (pinfunction "D+_A6") (pintype "bidirectional"))
      (node (ref "USB-NATIVE") (pin "B6") (pinfunction "D+_B6") (pintype "bidirectional"))
    )
    (net (code "91") (name "Net-(R40-Pad2)") (class "Default")
      (node (ref "R40") (pin "2") (pinfunction "2_2") (pintype "passive"))
      (node (ref "USB-NATIVE") (pin "A7") (pinfunction "D-_A7") (pintype "bidirectional"))
      (node (ref "USB-NATIVE") (pin "B7") (pinfunction "D-_B7") (pintype "bidirectional"))
    )
    (net (code "92") (name "Net-(R45-Pad1)") (class "Default")
      (node (ref "R45") (pin "1") (pinfunction "1_1") (pintype "passive"))
      (node (ref "STA") (pin "A") (pinfunction "A_A") (pintype "passive"))
    )
    (net (code "93") (name "Net-(R56-Pad1)") (class "Default")
      (node (ref "R56") (pin "1") (pinfunction "1_1") (pintype "passive"))
      (node (ref "U6") (pin "95") (pinfunction "NC_95") (pintype "bidirectional"))
    )
    (net (code "94") (name "Net-(R57-Pad1)") (class "Default")
      (node (ref "R57") (pin "1") (pinfunction "1_1") (pintype "passive"))
      (node (ref "U6") (pin "96") (pinfunction "NC_96") (pintype "bidirectional"))
    )
    (net (code "95") (name "Net-(U4-EN)") (class "Default")
      (node (ref "R77") (pin "1") (pinfunction "1_1") (pintype "passive"))
      (node (ref "U4") (pin "8") (pinfunction "EN_8") (pintype "bidirectional"))
    )
    (net (code "96") (name "Net-(U4-FB)") (class "Default")
      (node (ref "C61") (pin "1") (pinfunction "1_1") (pintype "passive"))
      (node (ref "R74") (pin "2") (pinfunction "2_2") (pintype "passive"))
      (node (ref "R75") (pin "1") (pinfunction "1_1") (pintype "passive"))
      (node (ref "U4") (pin "7") (pinfunction "FB_7") (pintype "bidirectional"))
    )
    (net (code "97") (name "Net-(U4-PG)") (class "Default")
      (node (ref "R76") (pin "1") (pinfunction "1_1") (pintype "passive"))
      (node (ref "U4") (pin "1") (pinfunction "PG_1") (pintype "bidirectional"))
    )
    (net (code "98") (name "Net-(U4-SW)") (class "Default")
      (node (ref "L2") (pin "1") (pinfunction "1_1") (pintype "passive"))
      (node (ref "U4") (pin "3") (pinfunction "SW_3") (pintype "bidirectional"))
    )
    (net (code "99") (name "Net-(U6-USIM1_CLK)") (class "Default")
      (node (ref "R32") (pin "1") (pinfunction "1_1") (pintype "passive"))
      (node (ref "U6") (pin "32") (pinfunction "USIM1_CLK_32") (pintype "bidirectional"))
    )
    (net (code "100") (name "Net-(U6-USIM1_DATA)") (class "Default")
      (node (ref "R31") (pin "1") (pinfunction "1_1") (pintype "passive"))
      (node (ref "U6") (pin "31") (pinfunction "USIM1_DATA_31") (pintype "bidirectional"))
    )
    (net (code "101") (name "Net-(U6-USIM1_RST)") (class "Default")
      (node (ref "R33") (pin "1") (pinfunction "1_1") (pintype "passive"))
      (node (ref "U6") (pin "33") (pinfunction "USIM1_RST_33") (pintype "bidirectional"))
    )
    (net (code "102") (name "Net-(U8-V)") (class "Default")
      (node (ref "R60") (pin "2") (pinfunction "2_2") (pintype "passive"))
      (node (ref "U8") (pin "1") (pinfunction "V_1") (pintype "bidirectional"))
    )
    (net (code "103") (name "Net-(U8-VDD)") (class "Default")
      (node (ref "C37") (pin "2") (pinfunction "2_2") (pintype "passive"))
      (node (ref "R62") (pin "2") (pinfunction "2_2") (pintype "passive"))
      (node (ref "U8") (pin "5") (pinfunction "VDD_5") (pintype "bidirectional"))
    )
    (net (code "104") (name "Net-(U9-CHRG)") (class "Default")
      (node (ref "CHRG") (pin "-") (pinfunction "-_-") (pintype "passive"))
      (node (ref "U9") (pin "3") (pinfunction "CHRG_3") (pintype "bidirectional"))
    )
    (net (code "105") (name "Net-(U9-COM)") (class "Default")
      (node (ref "R66") (pin "2") (pinfunction "2_2") (pintype "passive"))
      (node (ref "U9") (pin "5") (pinfunction "COM_5") (pintype "bidirectional"))
    )
    (net (code "106") (name "Net-(U9-CSP)") (class "Default")
      (node (ref "L3") (pin "2") (pinfunction "2_2") (pintype "passive"))
      (node (ref "R68") (pin "1") (pinfunction "1_1") (pintype "passive"))
      (node (ref "U9") (pin "8") (pinfunction "CSP_8") (pintype "bidirectional"))
    )
    (net (code "107") (name "Net-(U9-DONE)") (class "Default")
      (node (ref "DONE") (pin "-") (pinfunction "-_-") (pintype "passive"))
      (node (ref "U9") (pin "4") (pinfunction "DONE_4") (pintype "bidirectional"))
    )
    (net (code "108") (name "Net-(U9-MPPT)") (class "Default")
      (node (ref "R63") (pin "1") (pinfunction "1_1") (pintype "passive"))
      (node (ref "R64") (pin "2") (pinfunction "2_2") (pintype "passive"))
      (node (ref "U9") (pin "6") (pinfunction "MPPT_6") (pintype "bidirectional"))
    )
    (net (code "109") (name "Net-(U9-VG)") (class "Default")
      (node (ref "C38") (pin "2") (pinfunction "2_2") (pintype "passive"))
      (node (ref "U9") (pin "1") (pinfunction "VG_1") (pintype "bidirectional"))
    )
    (net (code "110") (name "Net-(USB-NATIVE-CC1)") (class "Default")
      (node (ref "R37") (pin "2") (pinfunction "2_2") (pintype "passive"))
      (node (ref "USB-NATIVE") (pin "A5") (pinfunction "CC1_A5") (pintype "bidirectional"))
    )
    (net (code "111") (name "Net-(USB-NATIVE-CC2)") (class "Default")
      (node (ref "R34") (pin "2") (pinfunction "2_2") (pintype "passive"))
      (node (ref "USB-NATIVE") (pin "B5") (pinfunction "CC2_B5") (pintype "bidirectional"))
    )
    (net (code "112") (name "VCC") (class "Default")
      (node (ref "C14") (pin "1") (pinfunction "1_1") (pintype "passive"))
      (node (ref "C15") (pin "1") (pinfunction "1_1") (pintype "passive"))
      (node (ref "C7") (pin "2") (pinfunction "2_2") (pintype "passive"))
      (node (ref "Q1") (pin "3") (pinfunction "D_3") (pintype "passive"))
      (node (ref "R11") (pin "2") (pinfunction "2_2") (pintype "passive"))
      (node (ref "R9") (pin "2") (pinfunction "2_2") (pintype "passive"))
      (node (ref "U3") (pin "4") (pinfunction "VDD_4") (pintype "bidirectional"))
      (node (ref "U5") (pin "13") (pinfunction "3.3V_13") (pintype "power_in"))
    )
    (net (code "113") (name "VDD") (class "Default")
      (node (ref "3V") (pin "T") (pinfunction "T_T") (pintype "bidirectional"))
      (node (ref "C30") (pin "2") (pinfunction "2_2") (pintype "passive"))
      (node (ref "C31") (pin "2") (pinfunction "2_2") (pintype "passive"))
      (node (ref "U6") (pin "99") (pinfunction "VDD_AUX_99") (pintype "bidirectional"))
    )
    (net (code "114") (name "V_BATT") (class "Default")
      (node (ref "C19") (pin "2") (pinfunction "2_2") (pintype "passive"))
      (node (ref "C20") (pin "2") (pinfunction "2_2") (pintype "passive"))
      (node (ref "C22") (pin "2") (pinfunction "2_2") (pintype "passive"))
      (node (ref "C23") (pin "2") (pinfunction "2_2") (pintype "passive"))
      (node (ref "C24") (pin "2") (pinfunction "2_2") (pintype "passive"))
      (node (ref "C26") (pin "A") (pinfunction "+_A") (pintype "passive"))
      (node (ref "C46") (pin "2") (pinfunction "2_2") (pintype "passive"))
      (node (ref "C47") (pin "2") (pinfunction "2_2") (pintype "passive"))
      (node (ref "C48") (pin "A") (pinfunction "+_A") (pintype "passive"))
      (node (ref "D7") (pin "-") (pinfunction "-_-") (pintype "passive"))
      (node (ref "D8") (pin "C") (pinfunction "C_C") (pintype "passive"))
      (node (ref "R22") (pin "2") (pinfunction "2_2") (pintype "passive"))
      (node (ref "R28") (pin "2") (pinfunction "2_2") (pintype "passive"))
      (node (ref "R45") (pin "2") (pinfunction "2_2") (pintype "passive"))
      (node (ref "R58") (pin "1") (pinfunction "1_1") (pintype "passive"))
      (node (ref "R78") (pin "1") (pinfunction "1_1") (pintype "passive"))
      (node (ref "U6") (pin "55") (pinfunction "VBAT_55") (pintype "bidirectional"))
      (node (ref "U6") (pin "56") (pinfunction "VBAT_56") (pintype "bidirectional"))
      (node (ref "U6") (pin "57") (pinfunction "VBAT_57") (pintype "bidirectional"))
    )
    (net (code "115") (name "unconnected-(D10-C1-Pad1)") (class "Default")
      (node (ref "D10") (pin "1") (pinfunction "C1_1") (pintype "passive"))
    )
    (net (code "116") (name "unconnected-(SIM-VPP-Pad6)") (class "Default")
      (node (ref "SIM") (pin "6") (pinfunction "VPP_6") (pintype "bidirectional"))
    )
    (net (code "117") (name "unconnected-(U1-IO3-Pad15)") (class "Default")
      (node (ref "U1") (pin "15") (pinfunction "IO3_15") (pintype "bidirectional"))
    )
    (net (code "118") (name "unconnected-(U1-IO9-Pad17)") (class "Default")
      (node (ref "U1") (pin "17") (pinfunction "IO9_17") (pintype "bidirectional"))
    )
    (net (code "119") (name "unconnected-(U1-IO10-Pad18)") (class "Default")
      (node (ref "U1") (pin "18") (pinfunction "IO10_18") (pintype "bidirectional"))
    )
    (net (code "120") (name "unconnected-(U1-IO16-Pad9)") (class "Default")
      (node (ref "U1") (pin "9") (pinfunction "IO16_9") (pintype "bidirectional"))
    )
    (net (code "121") (name "unconnected-(U1-IO35-Pad28)") (class "Default")
      (node (ref "U1") (pin "28") (pinfunction "IO35_28") (pintype "bidirectional"))
    )
    (net (code "122") (name "unconnected-(U1-IO36-Pad29)") (class "Default")
      (node (ref "U1") (pin "29") (pinfunction "IO36_29") (pintype "bidirectional"))
    )
    (net (code "123") (name "unconnected-(U1-IO37-Pad30)") (class "Default")
      (node (ref "U1") (pin "30") (pinfunction "IO37_30") (pintype "bidirectional"))
    )
    (net (code "124") (name "unconnected-(U1-IO45-Pad26)") (class "Default")
      (node (ref "U1") (pin "26") (pinfunction "IO45_26") (pintype "bidirectional"))
    )
    (net (code "125") (name "unconnected-(U1-IO46-Pad16)") (class "Default")
      (node (ref "U1") (pin "16") (pinfunction "IO46_16") (pintype "bidirectional"))
    )
    (net (code "126") (name "unconnected-(U2-BYP-Pad4)") (class "Default")
      (node (ref "U2") (pin "4") (pinfunction "BYP_4") (pintype "bidirectional"))
    )
    (net (code "127") (name "unconnected-(U3-NC-Pad6)") (class "Default")
      (node (ref "U3") (pin "6") (pinfunction "NC_6") (pintype "bidirectional"))
    )
    (net (code "128") (name "unconnected-(U5-DIO3-Pad11)") (class "Default")
      (node (ref "U5") (pin "11") (pinfunction "DIO3_11") (pintype "bidirectional"))
    )
    (net (code "129") (name "unconnected-(U5-DIO4-Pad12)") (class "Default")
      (node (ref "U5") (pin "12") (pinfunction "DIO4_12") (pintype "bidirectional"))
    )
    (net (code "130") (name "unconnected-(U5-DIO5-Pad7)") (class "Default")
      (node (ref "U5") (pin "7") (pinfunction "DIO5_7") (pintype "bidirectional"))
    )
    (net (code "131") (name "unconnected-(U6-ADC-Pad25)") (class "Default")
      (node (ref "U6") (pin "25") (pinfunction "ADC_25") (pintype "bidirectional"))
    )
    (net (code "132") (name "unconnected-(U6-CAM_I2C_SCL-Pad118)") (class "Default")
      (node (ref "U6") (pin "118") (pinfunction "CAM_I2C_SCL_118") (pintype "bidirectional"))
    )
    (net (code "133") (name "unconnected-(U6-CAM_I2C_SDA-Pad117)") (class "Default")
      (node (ref "U6") (pin "117") (pinfunction "CAM_I2C_SDA_117") (pintype "bidirectional"))
    )
    (net (code "134") (name "unconnected-(U6-CAM_MCLK-Pad121)") (class "Default")
      (node (ref "U6") (pin "121") (pinfunction "CAM_MCLK_121") (pintype "bidirectional"))
    )
    (net (code "135") (name "unconnected-(U6-CAM_PWDN-Pad119)") (class "Default")
      (node (ref "U6") (pin "119") (pinfunction "CAM_PWDN_119") (pintype "bidirectional"))
    )
    (net (code "136") (name "unconnected-(U6-CAM_RST-Pad120)") (class "Default")
      (node (ref "U6") (pin "120") (pinfunction "CAM_RST_120") (pintype "bidirectional"))
    )
    (net (code "137") (name "unconnected-(U6-CAM_SPI_CLK-Pad124)") (class "Default")
      (node (ref "U6") (pin "124") (pinfunction "CAM_SPI_CLK_124") (pintype "bidirectional"))
    )
    (net (code "138") (name "unconnected-(U6-CAM_SPI_D0-Pad122)") (class "Default")
      (node (ref "U6") (pin "122") (pinfunction "CAM_SPI_D0_122") (pintype "bidirectional"))
    )
    (net (code "139") (name "unconnected-(U6-CAM_SPI_D1-Pad123)") (class "Default")
      (node (ref "U6") (pin "123") (pinfunction "CAM_SPI_D1_123") (pintype "bidirectional"))
    )
    (net (code "140") (name "unconnected-(U6-CTS-Pad7)") (class "Default")
      (node (ref "U6") (pin "7") (pinfunction "CTS_7") (pintype "bidirectional"))
    )
    (net (code "141") (name "unconnected-(U6-DCD-Pad5)") (class "Default")
      (node (ref "U6") (pin "5") (pinfunction "DCD_5") (pintype "bidirectional"))
    )
    (net (code "142") (name "unconnected-(U6-EAR_N-Pad41)") (class "Default")
      (node (ref "U6") (pin "41") (pinfunction "EAR_N_41") (pintype "bidirectional"))
    )
    (net (code "143") (name "unconnected-(U6-EAR_P-Pad40)") (class "Default")
      (node (ref "U6") (pin "40") (pinfunction "EAR_P_40") (pintype "bidirectional"))
    )
    (net (code "144") (name "unconnected-(U6-GPIO1-Pad19)") (class "Default")
      (node (ref "U6") (pin "19") (pinfunction "GPIO1_19") (pintype "bidirectional"))
    )
    (net (code "145") (name "unconnected-(U6-GPIO2-Pad26)") (class "Default")
      (node (ref "U6") (pin "26") (pinfunction "GPIO2_26") (pintype "bidirectional"))
    )
    (net (code "146") (name "unconnected-(U6-GPIO3-Pad48)") (class "Default")
      (node (ref "U6") (pin "48") (pinfunction "GPIO3_48") (pintype "bidirectional"))
    )
    (net (code "147") (name "unconnected-(U6-GPIO4-Pad53)") (class "Default")
      (node (ref "U6") (pin "53") (pinfunction "GPIO4_53") (pintype "bidirectional"))
    )
    (net (code "148") (name "unconnected-(U6-I2C_SCL-Pad38)") (class "Default")
      (node (ref "U6") (pin "38") (pinfunction "I2C_SCL_38") (pintype "bidirectional"))
    )
    (net (code "149") (name "unconnected-(U6-I2C_SDA-Pad37)") (class "Default")
      (node (ref "U6") (pin "37") (pinfunction "I2C_SDA_37") (pintype "bidirectional"))
    )
    (net (code "150") (name "unconnected-(U6-LCD_BL_PWM-Pad101)") (class "Default")
      (node (ref "U6") (pin "101") (pinfunction "LCD_BL_PWM_101") (pintype "bidirectional"))
    )
    (net (code "151") (name "unconnected-(U6-LCD_DCX-Pad107)") (class "Default")
      (node (ref "U6") (pin "107") (pinfunction "LCD_DCX_107") (pintype "bidirectional"))
    )
    (net (code "152") (name "unconnected-(U6-LCD_RST-Pad106)") (class "Default")
      (node (ref "U6") (pin "106") (pinfunction "LCD_RST_106") (pintype "bidirectional"))
    )
    (net (code "153") (name "unconnected-(U6-LCD_SPI_CLK-Pad102)") (class "Default")
      (node (ref "U6") (pin "102") (pinfunction "LCD_SPI_CLK_102") (pintype "bidirectional"))
    )
    (net (code "154") (name "unconnected-(U6-LCD_SPI_CS-Pad105)") (class "Default")
      (node (ref "U6") (pin "105") (pinfunction "LCD_SPI_CS_105") (pintype "bidirectional"))
    )
    (net (code "155") (name "unconnected-(U6-LCD_SPI_RXD-Pad104)") (class "Default")
      (node (ref "U6") (pin "104") (pinfunction "LCD_SPI_RXD_104") (pintype "bidirectional"))
    )
    (net (code "156") (name "unconnected-(U6-LCD_SPI_TXD-Pad103)") (class "Default")
      (node (ref "U6") (pin "103") (pinfunction "LCD_SPI_TXD_103") (pintype "bidirectional"))
    )
    (net (code "157") (name "unconnected-(U6-MIC_N-Pad43)") (class "Default")
      (node (ref "U6") (pin "43") (pinfunction "MIC_N_43") (pintype "bidirectional"))
    )
    (net (code "158") (name "unconnected-(U6-MIC_P-Pad42)") (class "Default")
      (node (ref "U6") (pin "42") (pinfunction "MIC_P_42") (pintype "bidirectional"))
    )
    (net (code "159") (name "unconnected-(U6-MK_IN_2-Pad47)") (class "Default")
      (node (ref "U6") (pin "47") (pinfunction "MK_IN_2_47") (pintype "bidirectional"))
    )
    (net (code "160") (name "unconnected-(U6-MK_IN_5-Pad68)") (class "Default")
      (node (ref "U6") (pin "68") (pinfunction "MK_IN_5_68") (pintype "bidirectional"))
    )
    (net (code "161") (name "unconnected-(U6-MK_IN_6-Pad36)") (class "Default")
      (node (ref "U6") (pin "36") (pinfunction "MK_IN_6_36") (pintype "bidirectional"))
    )
    (net (code "162") (name "unconnected-(U6-MK_OUT_2-Pad44)") (class "Default")
      (node (ref "U6") (pin "44") (pinfunction "MK_OUT_2_44") (pintype "bidirectional"))
    )
    (net (code "163") (name "unconnected-(U6-MK_OUT_3-Pad21)") (class "Default")
      (node (ref "U6") (pin "21") (pinfunction "MK_OUT_3_21") (pintype "bidirectional"))
    )
    (net (code "164") (name "unconnected-(U6-MK_OUT_5-Pad67)") (class "Default")
      (node (ref "U6") (pin "67") (pinfunction "MK_OUT_5_67") (pintype "bidirectional"))
    )
    (net (code "165") (name "unconnected-(U6-MK_OUT_6-Pad35)") (class "Default")
      (node (ref "U6") (pin "35") (pinfunction "MK_OUT_6_35") (pintype "bidirectional"))
    )
    (net (code "166") (name "unconnected-(U6-NC-Pad93)") (class "Default")
      (node (ref "U6") (pin "93") (pinfunction "NC_93") (pintype "bidirectional"))
    )
    (net (code "167") (name "unconnected-(U6-NC-Pad100)") (class "Default")
      (node (ref "U6") (pin "100") (pinfunction "NC_100") (pintype "bidirectional"))
    )
    (net (code "168") (name "unconnected-(U6-NC-Pad113)") (class "Default")
      (node (ref "U6") (pin "113") (pinfunction "NC_113") (pintype "bidirectional"))
    )
    (net (code "169") (name "unconnected-(U6-NC-Pad114)") (class "Default")
      (node (ref "U6") (pin "114") (pinfunction "NC_114") (pintype "bidirectional"))
    )
    (net (code "170") (name "unconnected-(U6-NC-Pad115)") (class "Default")
      (node (ref "U6") (pin "115") (pinfunction "NC_115") (pintype "bidirectional"))
    )
    (net (code "171") (name "unconnected-(U6-RTS-Pad8)") (class "Default")
      (node (ref "U6") (pin "8") (pinfunction "RTS_8") (pintype "bidirectional"))
    )
    (net (code "172") (name "unconnected-(U6-SPI_CLK-Pad11)") (class "Default")
      (node (ref "U6") (pin "11") (pinfunction "SPI_CLK_11") (pintype "bidirectional"))
    )
    (net (code "173") (name "unconnected-(U6-SPI_CS-Pad12)") (class "Default")
      (node (ref "U6") (pin "12") (pinfunction "SPI_CS_12") (pintype "bidirectional"))
    )
    (net (code "174") (name "unconnected-(U6-SPI_MISO-Pad14)") (class "Default")
      (node (ref "U6") (pin "14") (pinfunction "SPI_MISO_14") (pintype "bidirectional"))
    )
    (net (code "175") (name "unconnected-(U6-SPI_MOSI-Pad13)") (class "Default")
      (node (ref "U6") (pin "13") (pinfunction "SPI_MOSI_13") (pintype "bidirectional"))
    )
    (net (code "176") (name "unconnected-(U6-USIM1_DET-Pad34)") (class "Default")
      (node (ref "U6") (pin "34") (pinfunction "USIM1_DET_34") (pintype "bidirectional"))
    )
    (net (code "177") (name "unconnected-(U6-USIM2_CLK-Pad109)") (class "Default")
      (node (ref "U6") (pin "109") (pinfunction "USIM2_CLK_109") (pintype "bidirectional"))
    )
    (net (code "178") (name "unconnected-(U6-USIM2_DATA-Pad108)") (class "Default")
      (node (ref "U6") (pin "108") (pinfunction "USIM2_DATA_108") (pintype "bidirectional"))
    )
    (net (code "179") (name "unconnected-(U6-USIM2_DET-Pad112)") (class "Default")
      (node (ref "U6") (pin "112") (pinfunction "USIM2_DET_112") (pintype "bidirectional"))
    )
    (net (code "180") (name "unconnected-(U6-USIM2_RST-Pad111)") (class "Default")
      (node (ref "U6") (pin "111") (pinfunction "USIM2_RST_111") (pintype "bidirectional"))
    )
    (net (code "181") (name "unconnected-(U6-USIM2_VDD-Pad110)") (class "Default")
      (node (ref "U6") (pin "110") (pinfunction "USIM2_VDD_110") (pintype "bidirectional"))
    )
    (net (code "182") (name "unconnected-(U8-D-Pad4)") (class "Default")
      (node (ref "U8") (pin "4") (pinfunction "D_4") (pintype "bidirectional"))
    )
  )
)
